# Y187.net
KiCad netlist of a schematic drawn in EAGLE
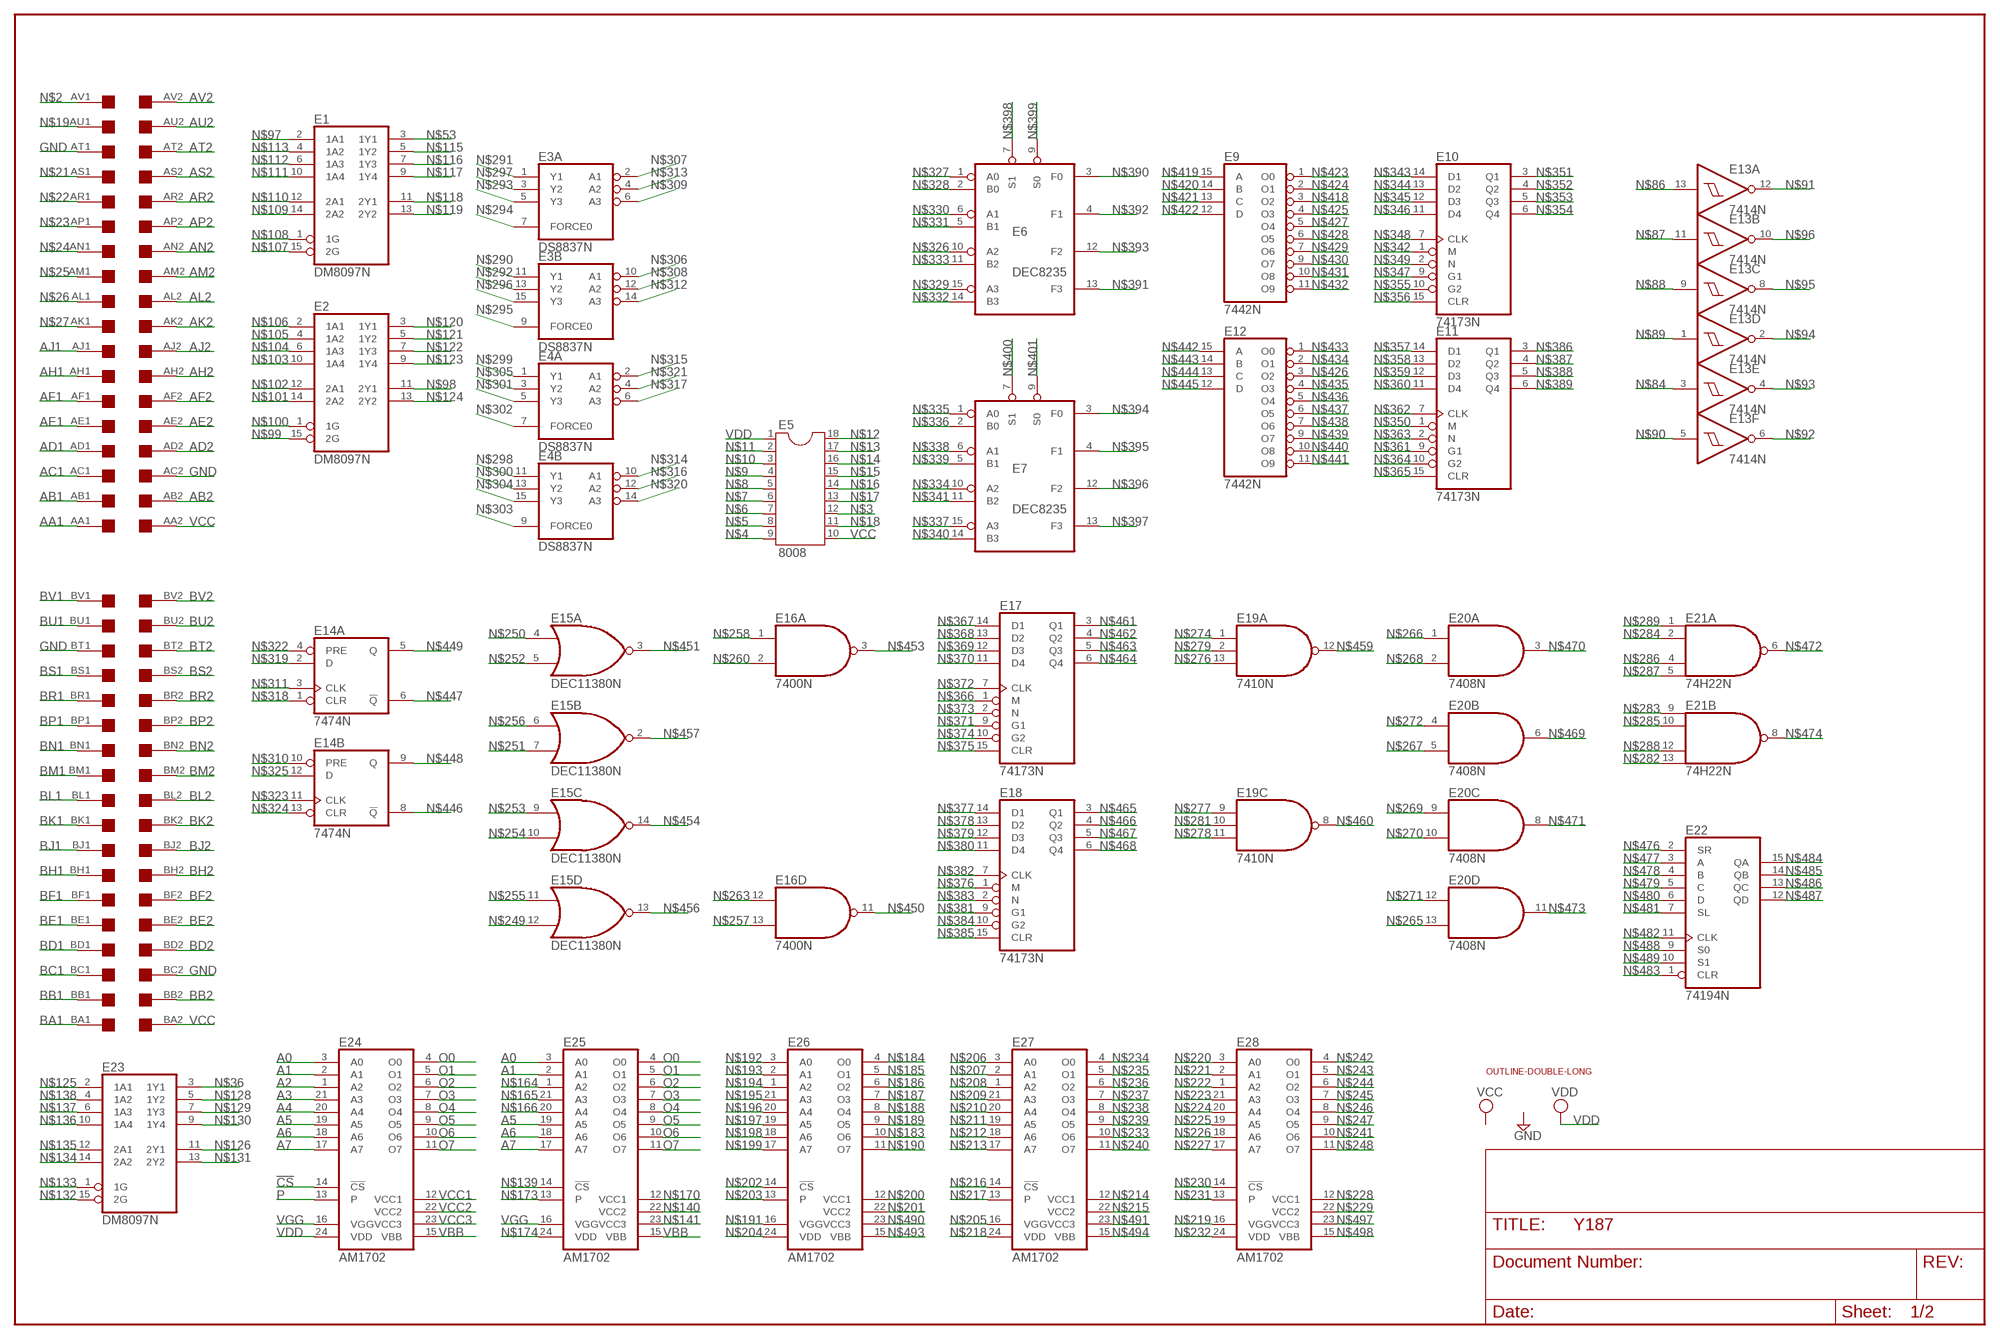
[diagram p0: schematic, sheet 1]
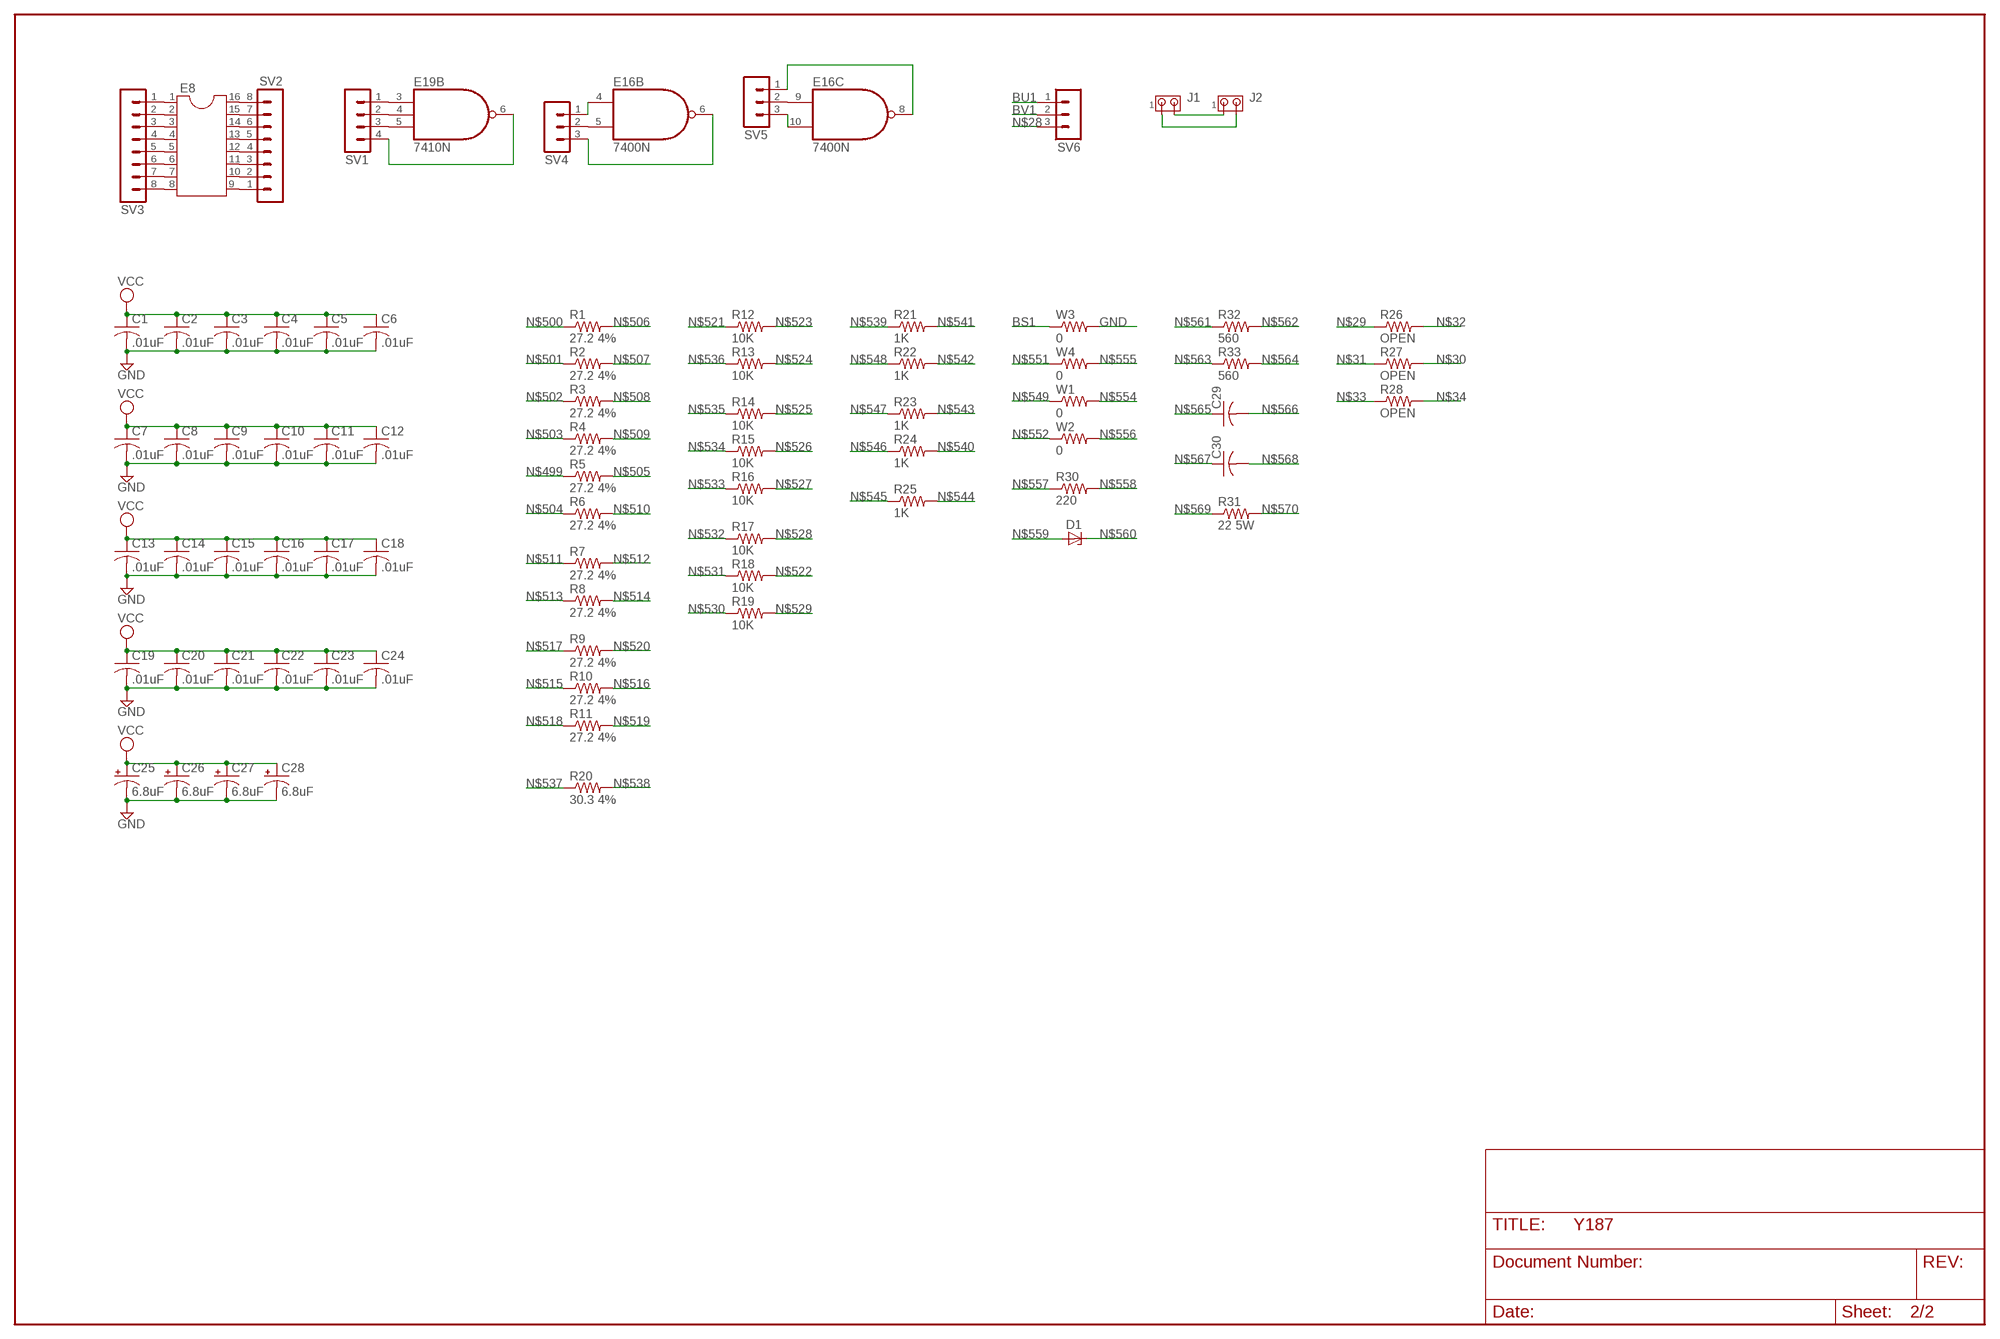
[diagram p1: schematic, sheet 2]

(export (version "E")
  (design (tool "Eeschema 10.0.6"))
  (components
    (comp (ref "C1")
      (value ".01uF")
      (footprint "eagle-import:C075-032X103")
      (libsource (lib "eagle-import") (part "C-US075-032X103"))
    )
    (comp (ref "C2")
      (value ".01uF")
      (footprint "eagle-import:C075-032X103")
      (libsource (lib "eagle-import") (part "C-US075-032X103"))
    )
    (comp (ref "C3")
      (value ".01uF")
      (footprint "eagle-import:C075-032X103")
      (libsource (lib "eagle-import") (part "C-US075-032X103"))
    )
    (comp (ref "C4")
      (value ".01uF")
      (footprint "eagle-import:C075-032X103")
      (libsource (lib "eagle-import") (part "C-US075-032X103"))
    )
    (comp (ref "C5")
      (value ".01uF")
      (footprint "eagle-import:C075-032X103")
      (libsource (lib "eagle-import") (part "C-US075-032X103"))
    )
    (comp (ref "C6")
      (value ".01uF")
      (footprint "eagle-import:C075-032X103")
      (libsource (lib "eagle-import") (part "C-US075-032X103"))
    )
    (comp (ref "C7")
      (value ".01uF")
      (footprint "eagle-import:C075-032X103")
      (libsource (lib "eagle-import") (part "C-US075-032X103"))
    )
    (comp (ref "C8")
      (value ".01uF")
      (footprint "eagle-import:C075-032X103")
      (libsource (lib "eagle-import") (part "C-US075-032X103"))
    )
    (comp (ref "C9")
      (value ".01uF")
      (footprint "eagle-import:C075-032X103")
      (libsource (lib "eagle-import") (part "C-US075-032X103"))
    )
    (comp (ref "C10")
      (value ".01uF")
      (footprint "eagle-import:C075-032X103")
      (libsource (lib "eagle-import") (part "C-US075-032X103"))
    )
    (comp (ref "C11")
      (value ".01uF")
      (footprint "eagle-import:C075-032X103")
      (libsource (lib "eagle-import") (part "C-US075-032X103"))
    )
    (comp (ref "C12")
      (value ".01uF")
      (footprint "eagle-import:C075-032X103")
      (libsource (lib "eagle-import") (part "C-US075-032X103"))
    )
    (comp (ref "C13")
      (value ".01uF")
      (footprint "eagle-import:C075-032X103")
      (libsource (lib "eagle-import") (part "C-US075-032X103"))
    )
    (comp (ref "C14")
      (value ".01uF")
      (footprint "eagle-import:C075-032X103")
      (libsource (lib "eagle-import") (part "C-US075-032X103"))
    )
    (comp (ref "C15")
      (value ".01uF")
      (footprint "eagle-import:C075-032X103")
      (libsource (lib "eagle-import") (part "C-US075-032X103"))
    )
    (comp (ref "C16")
      (value ".01uF")
      (footprint "eagle-import:C075-032X103")
      (libsource (lib "eagle-import") (part "C-US075-032X103"))
    )
    (comp (ref "C17")
      (value ".01uF")
      (footprint "eagle-import:C075-032X103")
      (libsource (lib "eagle-import") (part "C-US075-032X103"))
    )
    (comp (ref "C18")
      (value ".01uF")
      (footprint "eagle-import:C075-032X103")
      (libsource (lib "eagle-import") (part "C-US075-032X103"))
    )
    (comp (ref "C19")
      (value ".01uF")
      (footprint "eagle-import:C075-032X103")
      (libsource (lib "eagle-import") (part "C-US075-032X103"))
    )
    (comp (ref "C20")
      (value ".01uF")
      (footprint "eagle-import:C075-032X103")
      (libsource (lib "eagle-import") (part "C-US075-032X103"))
    )
    (comp (ref "C21")
      (value ".01uF")
      (footprint "eagle-import:C075-032X103")
      (libsource (lib "eagle-import") (part "C-US075-032X103"))
    )
    (comp (ref "C22")
      (value ".01uF")
      (footprint "eagle-import:C075-032X103")
      (libsource (lib "eagle-import") (part "C-US075-032X103"))
    )
    (comp (ref "C23")
      (value ".01uF")
      (footprint "eagle-import:C075-032X103")
      (libsource (lib "eagle-import") (part "C-US075-032X103"))
    )
    (comp (ref "C24")
      (value ".01uF")
      (footprint "eagle-import:C075-032X103")
      (libsource (lib "eagle-import") (part "C-US075-032X103"))
    )
    (comp (ref "C25")
      (value "6.8uF")
      (footprint "eagle-import:E12-8")
      (libsource (lib "eagle-import") (part "CPOL-USE20-8AXIAL"))
    )
    (comp (ref "C26")
      (value "6.8uF")
      (footprint "eagle-import:E12-8")
      (libsource (lib "eagle-import") (part "CPOL-USE20-8AXIAL"))
    )
    (comp (ref "C27")
      (value "6.8uF")
      (footprint "eagle-import:E12-8")
      (libsource (lib "eagle-import") (part "CPOL-USE20-8AXIAL"))
    )
    (comp (ref "C28")
      (value "6.8uF")
      (footprint "eagle-import:E12-8")
      (libsource (lib "eagle-import") (part "CPOL-USE20-8AXIAL"))
    )
    (comp (ref "C29")
      (value "C-US075-032X103")
      (footprint "eagle-import:C075-032X103")
      (libsource (lib "eagle-import") (part "C-US075-032X103"))
    )
    (comp (ref "C30")
      (value "C-US075-032X103")
      (footprint "eagle-import:C075-032X103")
      (libsource (lib "eagle-import") (part "C-US075-032X103"))
    )
    (comp (ref "D1")
      (value "ZENER-DIODEDO35Z10")
      (footprint "eagle-import:DO35Z10")
      (libsource (lib "eagle-import") (part "ZENER-DIODEDO35Z10"))
    )
    (comp (ref "E8")
      (value "DIL16")
      (footprint "eagle-import:DIL16")
      (libsource (lib "eagle-import") (part "DIL16"))
    )
    (comp (ref "E16")
      (value "7400N")
      (footprint "eagle-import:DIL14")
      (libsource (lib "eagle-import") (part "7400N"))
    )
    (comp (ref "E19")
      (value "7410N")
      (footprint "eagle-import:DIL14")
      (libsource (lib "eagle-import") (part "7410N"))
    )
    (comp (ref "J1")
      (value "MTA02-100")
      (footprint "eagle-import:10X02MTA")
      (libsource (lib "eagle-import") (part "MTA02-100"))
    )
    (comp (ref "J2")
      (value "MTA02-100")
      (footprint "eagle-import:10X02MTA")
      (libsource (lib "eagle-import") (part "MTA02-100"))
    )
    (comp (ref "R1")
      (value "27.2 4%")
      (footprint "eagle-import:0207_10")
      (libsource (lib "eagle-import") (part "R-US_0207/10"))
    )
    (comp (ref "R2")
      (value "27.2 4%")
      (footprint "eagle-import:0207_10")
      (libsource (lib "eagle-import") (part "R-US_0207/10"))
    )
    (comp (ref "R3")
      (value "27.2 4%")
      (footprint "eagle-import:0207_10")
      (libsource (lib "eagle-import") (part "R-US_0207/10"))
    )
    (comp (ref "R4")
      (value "27.2 4%")
      (footprint "eagle-import:0207_10")
      (libsource (lib "eagle-import") (part "R-US_0207/10"))
    )
    (comp (ref "R5")
      (value "27.2 4%")
      (footprint "eagle-import:0207_10")
      (libsource (lib "eagle-import") (part "R-US_0207/10"))
    )
    (comp (ref "R6")
      (value "27.2 4%")
      (footprint "eagle-import:0207_10")
      (libsource (lib "eagle-import") (part "R-US_0207/10"))
    )
    (comp (ref "R7")
      (value "27.2 4%")
      (footprint "eagle-import:0207_10")
      (libsource (lib "eagle-import") (part "R-US_0207/10"))
    )
    (comp (ref "R8")
      (value "27.2 4%")
      (footprint "eagle-import:0207_10")
      (libsource (lib "eagle-import") (part "R-US_0207/10"))
    )
    (comp (ref "R9")
      (value "27.2 4%")
      (footprint "eagle-import:0207_10")
      (libsource (lib "eagle-import") (part "R-US_0207/10"))
    )
    (comp (ref "R10")
      (value "27.2 4%")
      (footprint "eagle-import:0207_10")
      (libsource (lib "eagle-import") (part "R-US_0207/10"))
    )
    (comp (ref "R11")
      (value "27.2 4%")
      (footprint "eagle-import:0207_10")
      (libsource (lib "eagle-import") (part "R-US_0207/10"))
    )
    (comp (ref "R12")
      (value "10K")
      (footprint "eagle-import:0207_10")
      (libsource (lib "eagle-import") (part "R-US_0207/10"))
    )
    (comp (ref "R13")
      (value "10K")
      (footprint "eagle-import:0207_10")
      (libsource (lib "eagle-import") (part "R-US_0207/10"))
    )
    (comp (ref "R14")
      (value "10K")
      (footprint "eagle-import:0207_10")
      (libsource (lib "eagle-import") (part "R-US_0207/10"))
    )
    (comp (ref "R15")
      (value "10K")
      (footprint "eagle-import:0207_10")
      (libsource (lib "eagle-import") (part "R-US_0207/10"))
    )
    (comp (ref "R16")
      (value "10K")
      (footprint "eagle-import:0207_10")
      (libsource (lib "eagle-import") (part "R-US_0207/10"))
    )
    (comp (ref "R17")
      (value "10K")
      (footprint "eagle-import:0207_10")
      (libsource (lib "eagle-import") (part "R-US_0207/10"))
    )
    (comp (ref "R18")
      (value "10K")
      (footprint "eagle-import:0207_10")
      (libsource (lib "eagle-import") (part "R-US_0207/10"))
    )
    (comp (ref "R19")
      (value "10K")
      (footprint "eagle-import:0207_10")
      (libsource (lib "eagle-import") (part "R-US_0207/10"))
    )
    (comp (ref "R20")
      (value "30.3 4%")
      (footprint "eagle-import:0207_10")
      (libsource (lib "eagle-import") (part "R-US_0207/10"))
    )
    (comp (ref "R21")
      (value "1K")
      (footprint "eagle-import:0207_10")
      (libsource (lib "eagle-import") (part "R-US_0207/10"))
    )
    (comp (ref "R22")
      (value "1K")
      (footprint "eagle-import:0207_10")
      (libsource (lib "eagle-import") (part "R-US_0207/10"))
    )
    (comp (ref "R23")
      (value "1K")
      (footprint "eagle-import:0207_10")
      (libsource (lib "eagle-import") (part "R-US_0207/10"))
    )
    (comp (ref "R24")
      (value "1K")
      (footprint "eagle-import:0207_10")
      (libsource (lib "eagle-import") (part "R-US_0207/10"))
    )
    (comp (ref "R25")
      (value "1K")
      (footprint "eagle-import:0207_10")
      (libsource (lib "eagle-import") (part "R-US_0207/10"))
    )
    (comp (ref "R26")
      (value "OPEN")
      (footprint "eagle-import:0207_10")
      (libsource (lib "eagle-import") (part "R-US_0207/10"))
    )
    (comp (ref "R27")
      (value "OPEN")
      (footprint "eagle-import:0207_10")
      (libsource (lib "eagle-import") (part "R-US_0207/10"))
    )
    (comp (ref "R28")
      (value "OPEN")
      (footprint "eagle-import:0207_10")
      (libsource (lib "eagle-import") (part "R-US_0207/10"))
    )
    (comp (ref "R30")
      (value "220")
      (footprint "eagle-import:0207_10")
      (libsource (lib "eagle-import") (part "R-US_0207/10"))
    )
    (comp (ref "R31")
      (value "22 5W")
      (footprint "eagle-import:0617_22")
      (libsource (lib "eagle-import") (part "R-US_0617/22"))
    )
    (comp (ref "R32")
      (value "560")
      (footprint "eagle-import:0207_10")
      (libsource (lib "eagle-import") (part "R-US_0207/10"))
    )
    (comp (ref "R33")
      (value "560")
      (footprint "eagle-import:0207_10")
      (libsource (lib "eagle-import") (part "R-US_0207/10"))
    )
    (comp (ref "SV1")
      (value "MA04-1")
      (footprint "eagle-import:MA04-1")
      (libsource (lib "eagle-import") (part "MA04-1"))
    )
    (comp (ref "SV2")
      (value "MA08-1")
      (footprint "eagle-import:MA08-1")
      (libsource (lib "eagle-import") (part "MA08-1"))
    )
    (comp (ref "SV3")
      (value "MA08-1")
      (footprint "eagle-import:MA08-1")
      (libsource (lib "eagle-import") (part "MA08-1"))
    )
    (comp (ref "SV4")
      (value "MA03-1")
      (footprint "eagle-import:MA03-1")
      (libsource (lib "eagle-import") (part "MA03-1"))
    )
    (comp (ref "SV5")
      (value "MA03-1")
      (footprint "eagle-import:MA03-1")
      (libsource (lib "eagle-import") (part "MA03-1"))
    )
    (comp (ref "SV6")
      (value "MA03-1")
      (footprint "eagle-import:MA03-1")
      (libsource (lib "eagle-import") (part "MA03-1"))
    )
    (comp (ref "W1")
      (value "0")
      (footprint "eagle-import:0207_10")
      (libsource (lib "eagle-import") (part "R-US_0207/10"))
    )
    (comp (ref "W2")
      (value "0")
      (footprint "eagle-import:0207_10")
      (libsource (lib "eagle-import") (part "R-US_0207/10"))
    )
    (comp (ref "W3")
      (value "0")
      (footprint "eagle-import:0207_10")
      (libsource (lib "eagle-import") (part "R-US_0207/10"))
    )
    (comp (ref "W4")
      (value "0")
      (footprint "eagle-import:0207_10")
      (libsource (lib "eagle-import") (part "R-US_0207/10"))
    )
    (comp (ref "E1")
      (value "DM8097N")
      (footprint "eagle-import:DIL16")
      (libsource (lib "eagle-import") (part "74367N"))
    )
    (comp (ref "E2")
      (value "DM8097N")
      (footprint "eagle-import:DIL16")
      (libsource (lib "eagle-import") (part "74367N"))
    )
    (comp (ref "E3")
      (value "DS8837N")
      (footprint "eagle-import:DIL16")
      (libsource (lib "eagle-import") (part "DS8837N"))
    )
    (comp (ref "E4")
      (value "DS8837N")
      (footprint "eagle-import:DIL16")
      (libsource (lib "eagle-import") (part "DS8837N"))
    )
    (comp (ref "E5")
      (value "8008")
      (footprint "eagle-import:DIL18")
      (libsource (lib "eagle-import") (part "DIL18"))
    )
    (comp (ref "E6")
      (value "DEC8235")
      (footprint "eagle-import:DIL16")
      (libsource (lib "eagle-import") (part "DEC8235"))
    )
    (comp (ref "E7")
      (value "DEC8235")
      (footprint "eagle-import:DIL16")
      (libsource (lib "eagle-import") (part "DEC8235"))
    )
    (comp (ref "E9")
      (value "7442N")
      (footprint "eagle-import:DIL16")
      (libsource (lib "eagle-import") (part "7442NLS"))
    )
    (comp (ref "E10")
      (value "74173N")
      (footprint "eagle-import:DIL16")
      (libsource (lib "eagle-import") (part "74173NLS"))
    )
    (comp (ref "E11")
      (value "74173N")
      (footprint "eagle-import:DIL16")
      (libsource (lib "eagle-import") (part "74173NLS"))
    )
    (comp (ref "E12")
      (value "7442N")
      (footprint "eagle-import:DIL16")
      (libsource (lib "eagle-import") (part "7442NLS"))
    )
    (comp (ref "E13")
      (value "7414N")
      (footprint "eagle-import:DIL14")
      (libsource (lib "eagle-import") (part "7414N"))
    )
    (comp (ref "E14")
      (value "7474N")
      (footprint "eagle-import:DIL14")
      (libsource (lib "eagle-import") (part "7474NS"))
    )
    (comp (ref "E15")
      (value "DEC11380N")
      (footprint "eagle-import:DIL14")
      (libsource (lib "eagle-import") (part "SP380N"))
    )
    (comp (ref "E17")
      (value "74173N")
      (footprint "eagle-import:DIL16")
      (libsource (lib "eagle-import") (part "74173NLS"))
    )
    (comp (ref "E18")
      (value "74173N")
      (footprint "eagle-import:DIL16")
      (libsource (lib "eagle-import") (part "74173NLS"))
    )
    (comp (ref "E20")
      (value "7408N")
      (footprint "eagle-import:DIL14")
      (libsource (lib "eagle-import") (part "7408NLS"))
    )
    (comp (ref "E21")
      (value "74H22N")
      (footprint "eagle-import:DIL14")
      (libsource (lib "eagle-import") (part "7422N"))
    )
    (comp (ref "E22")
      (value "74194N")
      (footprint "eagle-import:DIL16")
      (libsource (lib "eagle-import") (part "74194NLS"))
    )
    (comp (ref "E23")
      (value "DM8097N")
      (footprint "eagle-import:DIL16")
      (libsource (lib "eagle-import") (part "74367N"))
    )
    (comp (ref "E24")
      (value "AM1702")
      (footprint "eagle-import:DIL24")
      (libsource (lib "eagle-import") (part "AM1702"))
    )
    (comp (ref "E25")
      (value "AM1702")
      (footprint "eagle-import:DIL24")
      (libsource (lib "eagle-import") (part "AM1702"))
    )
    (comp (ref "E26")
      (value "AM1702")
      (footprint "eagle-import:DIL24")
      (libsource (lib "eagle-import") (part "AM1702"))
    )
    (comp (ref "E27")
      (value "AM1702")
      (footprint "eagle-import:DIL24")
      (libsource (lib "eagle-import") (part "AM1702"))
    )
    (comp (ref "E28")
      (value "AM1702")
      (footprint "eagle-import:DIL24")
      (libsource (lib "eagle-import") (part "AM1702"))
    )
    (comp (ref "U$1")
      (value "OUTLINE-DOUBLE-LONG")
      (footprint "eagle-import:DOUBLE-LONG")
      (libsource (lib "eagle-import") (part "OUTLINE-DOUBLE-LONG"))
    )
    (comp (ref "U$2")
      (value "DOUBLE")
      (footprint "eagle-import:EDGE-CON4")
      (libsource (lib "eagle-import") (part "DOUBLE"))
    )
  )
  (nets
    (net (code "1") (name "A0") (class "Default")
      (node (ref "E24") (pin "3") (pinfunction "A0_3") (pintype "input"))
      (node (ref "E25") (pin "3") (pinfunction "A0_3") (pintype "input"))
    )
    (net (code "2") (name "A1") (class "Default")
      (node (ref "E24") (pin "2") (pinfunction "A1_2") (pintype "input"))
      (node (ref "E25") (pin "2") (pinfunction "A1_2") (pintype "input"))
    )
    (net (code "3") (name "A2") (class "Default")
      (node (ref "E24") (pin "1") (pinfunction "A2_1") (pintype "input"))
    )
    (net (code "4") (name "A3") (class "Default")
      (node (ref "E24") (pin "21") (pinfunction "A3_21") (pintype "input"))
    )
    (net (code "5") (name "A4") (class "Default")
      (node (ref "E24") (pin "20") (pinfunction "A4_20") (pintype "input"))
    )
    (net (code "6") (name "A5") (class "Default")
      (node (ref "E24") (pin "19") (pinfunction "A5_19") (pintype "input"))
      (node (ref "E25") (pin "19") (pinfunction "A5_19") (pintype "input"))
    )
    (net (code "7") (name "A6") (class "Default")
      (node (ref "E24") (pin "18") (pinfunction "A6_18") (pintype "input"))
      (node (ref "E25") (pin "18") (pinfunction "A6_18") (pintype "input"))
    )
    (net (code "8") (name "A7") (class "Default")
      (node (ref "E24") (pin "17") (pinfunction "A7_17") (pintype "input"))
      (node (ref "E25") (pin "17") (pinfunction "A7_17") (pintype "input"))
    )
    (net (code "9") (name "AA1") (class "Default")
      (node (ref "U$2") (pin "AA1") (pinfunction "1_AA1") (pintype "bidirectional"))
    )
    (net (code "10") (name "AB1") (class "Default")
      (node (ref "U$2") (pin "AB1") (pinfunction "1_AB1") (pintype "bidirectional"))
    )
    (net (code "11") (name "AB2") (class "Default")
      (node (ref "U$2") (pin "AB2") (pinfunction "1_AB2") (pintype "bidirectional"))
    )
    (net (code "12") (name "AC1") (class "Default")
      (node (ref "U$2") (pin "AC1") (pinfunction "1_AC1") (pintype "bidirectional"))
    )
    (net (code "13") (name "AD1") (class "Default")
      (node (ref "U$2") (pin "AD1") (pinfunction "1_AD1") (pintype "bidirectional"))
    )
    (net (code "14") (name "AD2") (class "Default")
      (node (ref "U$2") (pin "AD2") (pinfunction "1_AD2") (pintype "bidirectional"))
    )
    (net (code "15") (name "AE1") (class "Default")
      (node (ref "U$2") (pin "AE1") (pinfunction "1_AE1") (pintype "bidirectional"))
    )
    (net (code "16") (name "AE2") (class "Default")
      (node (ref "U$2") (pin "AE2") (pinfunction "1_AE2") (pintype "bidirectional"))
    )
    (net (code "17") (name "AF1") (class "Default")
      (node (ref "U$2") (pin "AF1") (pinfunction "1_AF1") (pintype "bidirectional"))
    )
    (net (code "18") (name "AF2") (class "Default")
      (node (ref "U$2") (pin "AF2") (pinfunction "1_AF2") (pintype "bidirectional"))
    )
    (net (code "19") (name "AH1") (class "Default")
      (node (ref "U$2") (pin "AH1") (pinfunction "1_AH1") (pintype "bidirectional"))
    )
    (net (code "20") (name "AH2") (class "Default")
      (node (ref "U$2") (pin "AH2") (pinfunction "1_AH2") (pintype "bidirectional"))
    )
    (net (code "21") (name "AJ1") (class "Default")
      (node (ref "U$2") (pin "AJ1") (pinfunction "1_AJ1") (pintype "bidirectional"))
    )
    (net (code "22") (name "AJ2") (class "Default")
      (node (ref "U$2") (pin "AJ2") (pinfunction "1_AJ2") (pintype "bidirectional"))
    )
    (net (code "23") (name "AK2") (class "Default")
      (node (ref "U$2") (pin "AK2") (pinfunction "1_AK2") (pintype "bidirectional"))
    )
    (net (code "24") (name "AL2") (class "Default")
      (node (ref "U$2") (pin "AL2") (pinfunction "1_AL2") (pintype "bidirectional"))
    )
    (net (code "25") (name "AM2") (class "Default")
      (node (ref "U$2") (pin "AM2") (pinfunction "1_AM2") (pintype "bidirectional"))
    )
    (net (code "26") (name "AN2") (class "Default")
      (node (ref "U$2") (pin "AN2") (pinfunction "1_AN2") (pintype "bidirectional"))
    )
    (net (code "27") (name "AP2") (class "Default")
      (node (ref "U$2") (pin "AP2") (pinfunction "1_AP2") (pintype "bidirectional"))
    )
    (net (code "28") (name "AR2") (class "Default")
      (node (ref "U$2") (pin "AR2") (pinfunction "1_AR2") (pintype "bidirectional"))
    )
    (net (code "29") (name "AS2") (class "Default")
      (node (ref "U$2") (pin "AS2") (pinfunction "1_AS2") (pintype "bidirectional"))
    )
    (net (code "30") (name "AT2") (class "Default")
      (node (ref "U$2") (pin "AT2") (pinfunction "1_AT2") (pintype "bidirectional"))
    )
    (net (code "31") (name "AU2") (class "Default")
      (node (ref "U$2") (pin "AU2") (pinfunction "1_AU2") (pintype "bidirectional"))
    )
    (net (code "32") (name "AV2") (class "Default")
      (node (ref "U$2") (pin "AV2") (pinfunction "1_AV2") (pintype "bidirectional"))
    )
    (net (code "33") (name "BA1") (class "Default")
      (node (ref "U$2") (pin "BA1") (pinfunction "1_BA1") (pintype "bidirectional"))
    )
    (net (code "34") (name "BB1") (class "Default")
      (node (ref "U$2") (pin "BB1") (pinfunction "1_BB1") (pintype "bidirectional"))
    )
    (net (code "35") (name "BB2") (class "Default")
      (node (ref "U$2") (pin "BB2") (pinfunction "1_BB2") (pintype "bidirectional"))
    )
    (net (code "36") (name "BC1") (class "Default")
      (node (ref "U$2") (pin "BC1") (pinfunction "1_BC1") (pintype "bidirectional"))
    )
    (net (code "37") (name "BD1") (class "Default")
      (node (ref "U$2") (pin "BD1") (pinfunction "1_BD1") (pintype "bidirectional"))
    )
    (net (code "38") (name "BD2") (class "Default")
      (node (ref "U$2") (pin "BD2") (pinfunction "1_BD2") (pintype "bidirectional"))
    )
    (net (code "39") (name "BE1") (class "Default")
      (node (ref "U$2") (pin "BE1") (pinfunction "1_BE1") (pintype "bidirectional"))
    )
    (net (code "40") (name "BE2") (class "Default")
      (node (ref "U$2") (pin "BE2") (pinfunction "1_BE2") (pintype "bidirectional"))
    )
    (net (code "41") (name "BF1") (class "Default")
      (node (ref "U$2") (pin "BF1") (pinfunction "1_BF1") (pintype "bidirectional"))
    )
    (net (code "42") (name "BF2") (class "Default")
      (node (ref "U$2") (pin "BF2") (pinfunction "1_BF2") (pintype "bidirectional"))
    )
    (net (code "43") (name "BH1") (class "Default")
      (node (ref "U$2") (pin "BH1") (pinfunction "1_BH1") (pintype "bidirectional"))
    )
    (net (code "44") (name "BH2") (class "Default")
      (node (ref "U$2") (pin "BH2") (pinfunction "1_BH2") (pintype "bidirectional"))
    )
    (net (code "45") (name "BJ1") (class "Default")
      (node (ref "U$2") (pin "BJ1") (pinfunction "1_BJ1") (pintype "bidirectional"))
    )
    (net (code "46") (name "BJ2") (class "Default")
      (node (ref "U$2") (pin "BJ2") (pinfunction "1_BJ2") (pintype "bidirectional"))
    )
    (net (code "47") (name "BK1") (class "Default")
      (node (ref "U$2") (pin "BK1") (pinfunction "1_BK1") (pintype "bidirectional"))
    )
    (net (code "48") (name "BK2") (class "Default")
      (node (ref "U$2") (pin "BK2") (pinfunction "1_BK2") (pintype "bidirectional"))
    )
    (net (code "49") (name "BL1") (class "Default")
      (node (ref "U$2") (pin "BL1") (pinfunction "1_BL1") (pintype "bidirectional"))
    )
    (net (code "50") (name "BL2") (class "Default")
      (node (ref "U$2") (pin "BL2") (pinfunction "1_BL2") (pintype "bidirectional"))
    )
    (net (code "51") (name "BM1") (class "Default")
      (node (ref "U$2") (pin "BM1") (pinfunction "1_BM1") (pintype "bidirectional"))
    )
    (net (code "52") (name "BM2") (class "Default")
      (node (ref "U$2") (pin "BM2") (pinfunction "1_BM2") (pintype "bidirectional"))
    )
    (net (code "53") (name "BN1") (class "Default")
      (node (ref "U$2") (pin "BN1") (pinfunction "1_BN1") (pintype "bidirectional"))
    )
    (net (code "54") (name "BN2") (class "Default")
      (node (ref "U$2") (pin "BN2") (pinfunction "1_BN2") (pintype "bidirectional"))
    )
    (net (code "55") (name "BP1") (class "Default")
      (node (ref "U$2") (pin "BP1") (pinfunction "1_BP1") (pintype "bidirectional"))
    )
    (net (code "56") (name "BP2") (class "Default")
      (node (ref "U$2") (pin "BP2") (pinfunction "1_BP2") (pintype "bidirectional"))
    )
    (net (code "57") (name "BR1") (class "Default")
      (node (ref "U$2") (pin "BR1") (pinfunction "1_BR1") (pintype "bidirectional"))
    )
    (net (code "58") (name "BR2") (class "Default")
      (node (ref "U$2") (pin "BR2") (pinfunction "1_BR2") (pintype "bidirectional"))
    )
    (net (code "59") (name "BS1") (class "Default")
      (node (ref "U$2") (pin "BS1") (pinfunction "1_BS1") (pintype "bidirectional"))
      (node (ref "W3") (pin "1") (pinfunction "1_1") (pintype "passive"))
    )
    (net (code "60") (name "BS2") (class "Default")
      (node (ref "U$2") (pin "BS2") (pinfunction "1_BS2") (pintype "bidirectional"))
    )
    (net (code "61") (name "BT2") (class "Default")
      (node (ref "U$2") (pin "BT2") (pinfunction "1_BT2") (pintype "bidirectional"))
    )
    (net (code "62") (name "BU1") (class "Default")
      (node (ref "SV6") (pin "1") (pinfunction "1_1") (pintype "passive"))
      (node (ref "U$2") (pin "BU1") (pinfunction "1_BU1") (pintype "bidirectional"))
    )
    (net (code "63") (name "BU2") (class "Default")
      (node (ref "U$2") (pin "BU2") (pinfunction "1_BU2") (pintype "bidirectional"))
    )
    (net (code "64") (name "BV1") (class "Default")
      (node (ref "SV6") (pin "2") (pinfunction "2_2") (pintype "passive"))
      (node (ref "U$2") (pin "BV1") (pinfunction "1_BV1") (pintype "bidirectional"))
    )
    (net (code "65") (name "BV2") (class "Default")
      (node (ref "U$2") (pin "BV2") (pinfunction "1_BV2") (pintype "bidirectional"))
    )
    (net (code "66") (name "GND") (class "Default")
      (node (ref "C1") (pin "2") (pinfunction "2_2") (pintype "passive"))
      (node (ref "C10") (pin "2") (pinfunction "2_2") (pintype "passive"))
      (node (ref "C11") (pin "2") (pinfunction "2_2") (pintype "passive"))
      (node (ref "C12") (pin "2") (pinfunction "2_2") (pintype "passive"))
      (node (ref "C13") (pin "2") (pinfunction "2_2") (pintype "passive"))
      (node (ref "C14") (pin "2") (pinfunction "2_2") (pintype "passive"))
      (node (ref "C15") (pin "2") (pinfunction "2_2") (pintype "passive"))
      (node (ref "C16") (pin "2") (pinfunction "2_2") (pintype "passive"))
      (node (ref "C17") (pin "2") (pinfunction "2_2") (pintype "passive"))
      (node (ref "C18") (pin "2") (pinfunction "2_2") (pintype "passive"))
      (node (ref "C19") (pin "2") (pinfunction "2_2") (pintype "passive"))
      (node (ref "C2") (pin "2") (pinfunction "2_2") (pintype "passive"))
      (node (ref "C20") (pin "2") (pinfunction "2_2") (pintype "passive"))
      (node (ref "C21") (pin "2") (pinfunction "2_2") (pintype "passive"))
      (node (ref "C22") (pin "2") (pinfunction "2_2") (pintype "passive"))
      (node (ref "C23") (pin "2") (pinfunction "2_2") (pintype "passive"))
      (node (ref "C24") (pin "2") (pinfunction "2_2") (pintype "passive"))
      (node (ref "C25") (pin "-") (pinfunction "-_-") (pintype "passive"))
      (node (ref "C26") (pin "-") (pinfunction "-_-") (pintype "passive"))
      (node (ref "C27") (pin "-") (pinfunction "-_-") (pintype "passive"))
      (node (ref "C28") (pin "-") (pinfunction "-_-") (pintype "passive"))
      (node (ref "C3") (pin "2") (pinfunction "2_2") (pintype "passive"))
      (node (ref "C4") (pin "2") (pinfunction "2_2") (pintype "passive"))
      (node (ref "C5") (pin "2") (pinfunction "2_2") (pintype "passive"))
      (node (ref "C6") (pin "2") (pinfunction "2_2") (pintype "passive"))
      (node (ref "C7") (pin "2") (pinfunction "2_2") (pintype "passive"))
      (node (ref "C8") (pin "2") (pinfunction "2_2") (pintype "passive"))
      (node (ref "C9") (pin "2") (pinfunction "2_2") (pintype "passive"))
      (node (ref "U$2") (pin "AC2") (pinfunction "1_AC2") (pintype "bidirectional"))
      (node (ref "U$2") (pin "AT1") (pinfunction "1_AT1") (pintype "bidirectional"))
      (node (ref "U$2") (pin "BC2") (pinfunction "1_BC2") (pintype "bidirectional"))
      (node (ref "U$2") (pin "BT1") (pinfunction "1_BT1") (pintype "bidirectional"))
      (node (ref "W3") (pin "2") (pinfunction "2_2") (pintype "passive"))
    )
    (net (code "67") (name "N$2") (class "Default")
      (node (ref "U$2") (pin "AV1") (pinfunction "1_AV1") (pintype "bidirectional"))
    )
    (net (code "68") (name "N$3") (class "Default")
      (node (ref "E5") (pin "12") (pinfunction "12_12") (pintype "passive"))
    )
    (net (code "69") (name "N$4") (class "Default")
      (node (ref "E5") (pin "9") (pinfunction "9_9") (pintype "passive"))
    )
    (net (code "70") (name "N$5") (class "Default")
      (node (ref "E5") (pin "8") (pinfunction "8_8") (pintype "passive"))
    )
    (net (code "71") (name "N$6") (class "Default")
      (node (ref "E5") (pin "7") (pinfunction "7_7") (pintype "passive"))
    )
    (net (code "72") (name "N$7") (class "Default")
      (node (ref "E5") (pin "6") (pinfunction "6_6") (pintype "passive"))
    )
    (net (code "73") (name "N$8") (class "Default")
      (node (ref "E5") (pin "5") (pinfunction "5_5") (pintype "passive"))
    )
    (net (code "74") (name "N$9") (class "Default")
      (node (ref "E5") (pin "4") (pinfunction "4_4") (pintype "passive"))
    )
    (net (code "75") (name "N$10") (class "Default")
      (node (ref "E5") (pin "3") (pinfunction "3_3") (pintype "passive"))
    )
    (net (code "76") (name "N$11") (class "Default")
      (node (ref "E5") (pin "2") (pinfunction "2_2") (pintype "passive"))
    )
    (net (code "77") (name "N$12") (class "Default")
      (node (ref "E5") (pin "18") (pinfunction "18_18") (pintype "passive"))
    )
    (net (code "78") (name "N$13") (class "Default")
      (node (ref "E5") (pin "17") (pinfunction "17_17") (pintype "passive"))
    )
    (net (code "79") (name "N$14") (class "Default")
      (node (ref "E5") (pin "16") (pinfunction "16_16") (pintype "passive"))
    )
    (net (code "80") (name "N$15") (class "Default")
      (node (ref "E5") (pin "15") (pinfunction "15_15") (pintype "passive"))
    )
    (net (code "81") (name "N$16") (class "Default")
      (node (ref "E5") (pin "14") (pinfunction "14_14") (pintype "passive"))
    )
    (net (code "82") (name "N$17") (class "Default")
      (node (ref "E5") (pin "13") (pinfunction "13_13") (pintype "passive"))
    )
    (net (code "83") (name "N$18") (class "Default")
      (node (ref "E5") (pin "11") (pinfunction "11_11") (pintype "passive"))
    )
    (net (code "84") (name "N$19") (class "Default")
      (node (ref "U$2") (pin "AU1") (pinfunction "1_AU1") (pintype "bidirectional"))
    )
    (net (code "85") (name "N$21") (class "Default")
      (node (ref "U$2") (pin "AS1") (pinfunction "1_AS1") (pintype "bidirectional"))
    )
    (net (code "86") (name "N$22") (class "Default")
      (node (ref "U$2") (pin "AR1") (pinfunction "1_AR1") (pintype "bidirectional"))
    )
    (net (code "87") (name "N$23") (class "Default")
      (node (ref "U$2") (pin "AP1") (pinfunction "1_AP1") (pintype "bidirectional"))
    )
    (net (code "88") (name "N$24") (class "Default")
      (node (ref "U$2") (pin "AN1") (pinfunction "1_AN1") (pintype "bidirectional"))
    )
    (net (code "89") (name "N$25") (class "Default")
      (node (ref "U$2") (pin "AM1") (pinfunction "1_AM1") (pintype "bidirectional"))
    )
    (net (code "90") (name "N$26") (class "Default")
      (node (ref "U$2") (pin "AL1") (pinfunction "1_AL1") (pintype "bidirectional"))
    )
    (net (code "91") (name "N$27") (class "Default")
      (node (ref "U$2") (pin "AK1") (pinfunction "1_AK1") (pintype "bidirectional"))
    )
    (net (code "92") (name "N$28") (class "Default")
      (node (ref "SV6") (pin "3") (pinfunction "3_3") (pintype "passive"))
    )
    (net (code "93") (name "N$29") (class "Default")
      (node (ref "R26") (pin "1") (pinfunction "1_1") (pintype "passive"))
    )
    (net (code "94") (name "N$30") (class "Default")
      (node (ref "R27") (pin "2") (pinfunction "2_2") (pintype "passive"))
    )
    (net (code "95") (name "N$31") (class "Default")
      (node (ref "R27") (pin "1") (pinfunction "1_1") (pintype "passive"))
    )
    (net (code "96") (name "N$32") (class "Default")
      (node (ref "R26") (pin "2") (pinfunction "2_2") (pintype "passive"))
    )
    (net (code "97") (name "N$33") (class "Default")
      (node (ref "R28") (pin "1") (pinfunction "1_1") (pintype "passive"))
    )
    (net (code "98") (name "N$34") (class "Default")
      (node (ref "R28") (pin "2") (pinfunction "2_2") (pintype "passive"))
    )
    (net (code "99") (name "N$36") (class "Default")
      (node (ref "E23") (pin "3") (pinfunction "1Y1_3") (pintype "tri_state"))
    )
    (net (code "100") (name "N$53") (class "Default")
      (node (ref "E1") (pin "3") (pinfunction "1Y1_3") (pintype "tri_state"))
    )
    (net (code "101") (name "N$84") (class "Default")
      (node (ref "E13") (pin "3") (pinfunction "I_3") (pintype "input"))
    )
    (net (code "102") (name "N$86") (class "Default")
      (node (ref "E13") (pin "13") (pinfunction "I_13") (pintype "input"))
    )
    (net (code "103") (name "N$87") (class "Default")
      (node (ref "E13") (pin "11") (pinfunction "I_11") (pintype "input"))
    )
    (net (code "104") (name "N$88") (class "Default")
      (node (ref "E13") (pin "9") (pinfunction "I_9") (pintype "input"))
    )
    (net (code "105") (name "N$89") (class "Default")
      (node (ref "E13") (pin "1") (pinfunction "I_1") (pintype "input"))
    )
    (net (code "106") (name "N$90") (class "Default")
      (node (ref "E13") (pin "5") (pinfunction "I_5") (pintype "input"))
    )
    (net (code "107") (name "N$91") (class "Default")
      (node (ref "E13") (pin "12") (pinfunction "O_12") (pintype "output"))
    )
    (net (code "108") (name "N$92") (class "Default")
      (node (ref "E13") (pin "6") (pinfunction "O_6") (pintype "output"))
    )
    (net (code "109") (name "N$93") (class "Default")
      (node (ref "E13") (pin "4") (pinfunction "O_4") (pintype "output"))
    )
    (net (code "110") (name "N$94") (class "Default")
      (node (ref "E13") (pin "2") (pinfunction "O_2") (pintype "output"))
    )
    (net (code "111") (name "N$95") (class "Default")
      (node (ref "E13") (pin "8") (pinfunction "O_8") (pintype "output"))
    )
    (net (code "112") (name "N$96") (class "Default")
      (node (ref "E13") (pin "10") (pinfunction "O_10") (pintype "output"))
    )
    (net (code "113") (name "N$97") (class "Default")
      (node (ref "E1") (pin "2") (pinfunction "1A1_2") (pintype "input"))
    )
    (net (code "114") (name "N$98") (class "Default")
      (node (ref "E2") (pin "11") (pinfunction "2Y1_11") (pintype "tri_state"))
    )
    (net (code "115") (name "N$99") (class "Default")
      (node (ref "E2") (pin "15") (pinfunction "2G_15") (pintype "input"))
    )
    (net (code "116") (name "N$100") (class "Default")
      (node (ref "E2") (pin "1") (pinfunction "1G_1") (pintype "input"))
    )
    (net (code "117") (name "N$101") (class "Default")
      (node (ref "E2") (pin "14") (pinfunction "2A2_14") (pintype "input"))
    )
    (net (code "118") (name "N$102") (class "Default")
      (node (ref "E2") (pin "12") (pinfunction "2A1_12") (pintype "input"))
    )
    (net (code "119") (name "N$103") (class "Default")
      (node (ref "E2") (pin "10") (pinfunction "1A4_10") (pintype "input"))
    )
    (net (code "120") (name "N$104") (class "Default")
      (node (ref "E2") (pin "6") (pinfunction "1A3_6") (pintype "input"))
    )
    (net (code "121") (name "N$105") (class "Default")
      (node (ref "E2") (pin "4") (pinfunction "1A2_4") (pintype "input"))
    )
    (net (code "122") (name "N$106") (class "Default")
      (node (ref "E2") (pin "2") (pinfunction "1A1_2") (pintype "input"))
    )
    (net (code "123") (name "N$107") (class "Default")
      (node (ref "E1") (pin "15") (pinfunction "2G_15") (pintype "input"))
    )
    (net (code "124") (name "N$108") (class "Default")
      (node (ref "E1") (pin "1") (pinfunction "1G_1") (pintype "input"))
    )
    (net (code "125") (name "N$109") (class "Default")
      (node (ref "E1") (pin "14") (pinfunction "2A2_14") (pintype "input"))
    )
    (net (code "126") (name "N$110") (class "Default")
      (node (ref "E1") (pin "12") (pinfunction "2A1_12") (pintype "input"))
    )
    (net (code "127") (name "N$111") (class "Default")
      (node (ref "E1") (pin "10") (pinfunction "1A4_10") (pintype "input"))
    )
    (net (code "128") (name "N$112") (class "Default")
      (node (ref "E1") (pin "6") (pinfunction "1A3_6") (pintype "input"))
    )
    (net (code "129") (name "N$113") (class "Default")
      (node (ref "E1") (pin "4") (pinfunction "1A2_4") (pintype "input"))
    )
    (net (code "130") (name "N$115") (class "Default")
      (node (ref "E1") (pin "5") (pinfunction "1Y2_5") (pintype "tri_state"))
    )
    (net (code "131") (name "N$116") (class "Default")
      (node (ref "E1") (pin "7") (pinfunction "1Y3_7") (pintype "tri_state"))
    )
    (net (code "132") (name "N$117") (class "Default")
      (node (ref "E1") (pin "9") (pinfunction "1Y4_9") (pintype "tri_state"))
    )
    (net (code "133") (name "N$118") (class "Default")
      (node (ref "E1") (pin "11") (pinfunction "2Y1_11") (pintype "tri_state"))
    )
    (net (code "134") (name "N$119") (class "Default")
      (node (ref "E1") (pin "13") (pinfunction "2Y2_13") (pintype "tri_state"))
    )
    (net (code "135") (name "N$120") (class "Default")
      (node (ref "E2") (pin "3") (pinfunction "1Y1_3") (pintype "tri_state"))
    )
    (net (code "136") (name "N$121") (class "Default")
      (node (ref "E2") (pin "5") (pinfunction "1Y2_5") (pintype "tri_state"))
    )
    (net (code "137") (name "N$122") (class "Default")
      (node (ref "E2") (pin "7") (pinfunction "1Y3_7") (pintype "tri_state"))
    )
    (net (code "138") (name "N$123") (class "Default")
      (node (ref "E2") (pin "9") (pinfunction "1Y4_9") (pintype "tri_state"))
    )
    (net (code "139") (name "N$124") (class "Default")
      (node (ref "E2") (pin "13") (pinfunction "2Y2_13") (pintype "tri_state"))
    )
    (net (code "140") (name "N$125") (class "Default")
      (node (ref "E23") (pin "2") (pinfunction "1A1_2") (pintype "input"))
    )
    (net (code "141") (name "N$126") (class "Default")
      (node (ref "E23") (pin "11") (pinfunction "2Y1_11") (pintype "tri_state"))
    )
    (net (code "142") (name "N$128") (class "Default")
      (node (ref "E23") (pin "5") (pinfunction "1Y2_5") (pintype "tri_state"))
    )
    (net (code "143") (name "N$129") (class "Default")
      (node (ref "E23") (pin "7") (pinfunction "1Y3_7") (pintype "tri_state"))
    )
    (net (code "144") (name "N$130") (class "Default")
      (node (ref "E23") (pin "9") (pinfunction "1Y4_9") (pintype "tri_state"))
    )
    (net (code "145") (name "N$131") (class "Default")
      (node (ref "E23") (pin "13") (pinfunction "2Y2_13") (pintype "tri_state"))
    )
    (net (code "146") (name "N$132") (class "Default")
      (node (ref "E23") (pin "15") (pinfunction "2G_15") (pintype "input"))
    )
    (net (code "147") (name "N$133") (class "Default")
      (node (ref "E23") (pin "1") (pinfunction "1G_1") (pintype "input"))
    )
    (net (code "148") (name "N$134") (class "Default")
      (node (ref "E23") (pin "14") (pinfunction "2A2_14") (pintype "input"))
    )
    (net (code "149") (name "N$135") (class "Default")
      (node (ref "E23") (pin "12") (pinfunction "2A1_12") (pintype "input"))
    )
    (net (code "150") (name "N$136") (class "Default")
      (node (ref "E23") (pin "10") (pinfunction "1A4_10") (pintype "input"))
    )
    (net (code "151") (name "N$137") (class "Default")
      (node (ref "E23") (pin "6") (pinfunction "1A3_6") (pintype "input"))
    )
    (net (code "152") (name "N$138") (class "Default")
      (node (ref "E23") (pin "4") (pinfunction "1A2_4") (pintype "input"))
    )
    (net (code "153") (name "N$139") (class "Default")
      (node (ref "E25") (pin "14") (pinfunction "~{CS}_14") (pintype "input"))
    )
    (net (code "154") (name "N$140") (class "Default")
      (node (ref "E25") (pin "22") (pinfunction "VCC2_22") (pintype "input"))
    )
    (net (code "155") (name "N$141") (class "Default")
      (node (ref "E25") (pin "23") (pinfunction "VCC3_23") (pintype "input"))
    )
    (net (code "156") (name "N$164") (class "Default")
      (node (ref "E25") (pin "1") (pinfunction "A2_1") (pintype "input"))
    )
    (net (code "157") (name "N$165") (class "Default")
      (node (ref "E25") (pin "21") (pinfunction "A3_21") (pintype "input"))
    )
    (net (code "158") (name "N$166") (class "Default")
      (node (ref "E25") (pin "20") (pinfunction "A4_20") (pintype "input"))
    )
    (net (code "159") (name "N$170") (class "Default")
      (node (ref "E25") (pin "12") (pinfunction "VCC1_12") (pintype "input"))
    )
    (net (code "160") (name "N$173") (class "Default")
      (node (ref "E25") (pin "13") (pinfunction "P_13") (pintype "input"))
    )
    (net (code "161") (name "N$174") (class "Default")
      (node (ref "E25") (pin "24") (pinfunction "VDD_24") (pintype "input"))
    )
    (net (code "162") (name "N$183") (class "Default")
      (node (ref "E26") (pin "10") (pinfunction "O6_10") (pintype "tri_state"))
    )
    (net (code "163") (name "N$184") (class "Default")
      (node (ref "E26") (pin "4") (pinfunction "O0_4") (pintype "tri_state"))
    )
    (net (code "164") (name "N$185") (class "Default")
      (node (ref "E26") (pin "5") (pinfunction "O1_5") (pintype "tri_state"))
    )
    (net (code "165") (name "N$186") (class "Default")
      (node (ref "E26") (pin "6") (pinfunction "O2_6") (pintype "tri_state"))
    )
    (net (code "166") (name "N$187") (class "Default")
      (node (ref "E26") (pin "7") (pinfunction "O3_7") (pintype "tri_state"))
    )
    (net (code "167") (name "N$188") (class "Default")
      (node (ref "E26") (pin "8") (pinfunction "O4_8") (pintype "tri_state"))
    )
    (net (code "168") (name "N$189") (class "Default")
      (node (ref "E26") (pin "9") (pinfunction "O5_9") (pintype "tri_state"))
    )
    (net (code "169") (name "N$190") (class "Default")
      (node (ref "E26") (pin "11") (pinfunction "O7_11") (pintype "tri_state"))
    )
    (net (code "170") (name "N$191") (class "Default")
      (node (ref "E26") (pin "16") (pinfunction "VGG_16") (pintype "input"))
    )
    (net (code "171") (name "N$192") (class "Default")
      (node (ref "E26") (pin "3") (pinfunction "A0_3") (pintype "input"))
    )
    (net (code "172") (name "N$193") (class "Default")
      (node (ref "E26") (pin "2") (pinfunction "A1_2") (pintype "input"))
    )
    (net (code "173") (name "N$194") (class "Default")
      (node (ref "E26") (pin "1") (pinfunction "A2_1") (pintype "input"))
    )
    (net (code "174") (name "N$195") (class "Default")
      (node (ref "E26") (pin "21") (pinfunction "A3_21") (pintype "input"))
    )
    (net (code "175") (name "N$196") (class "Default")
      (node (ref "E26") (pin "20") (pinfunction "A4_20") (pintype "input"))
    )
    (net (code "176") (name "N$197") (class "Default")
      (node (ref "E26") (pin "19") (pinfunction "A5_19") (pintype "input"))
    )
    (net (code "177") (name "N$198") (class "Default")
      (node (ref "E26") (pin "18") (pinfunction "A6_18") (pintype "input"))
    )
    (net (code "178") (name "N$199") (class "Default")
      (node (ref "E26") (pin "17") (pinfunction "A7_17") (pintype "input"))
    )
    (net (code "179") (name "N$200") (class "Default")
      (node (ref "E26") (pin "12") (pinfunction "VCC1_12") (pintype "input"))
    )
    (net (code "180") (name "N$201") (class "Default")
      (node (ref "E26") (pin "22") (pinfunction "VCC2_22") (pintype "input"))
    )
    (net (code "181") (name "N$202") (class "Default")
      (node (ref "E26") (pin "14") (pinfunction "~{CS}_14") (pintype "input"))
    )
    (net (code "182") (name "N$203") (class "Default")
      (node (ref "E26") (pin "13") (pinfunction "P_13") (pintype "input"))
    )
    (net (code "183") (name "N$204") (class "Default")
      (node (ref "E26") (pin "24") (pinfunction "VDD_24") (pintype "input"))
    )
    (net (code "184") (name "N$205") (class "Default")
      (node (ref "E27") (pin "16") (pinfunction "VGG_16") (pintype "input"))
    )
    (net (code "185") (name "N$206") (class "Default")
      (node (ref "E27") (pin "3") (pinfunction "A0_3") (pintype "input"))
    )
    (net (code "186") (name "N$207") (class "Default")
      (node (ref "E27") (pin "2") (pinfunction "A1_2") (pintype "input"))
    )
    (net (code "187") (name "N$208") (class "Default")
      (node (ref "E27") (pin "1") (pinfunction "A2_1") (pintype "input"))
    )
    (net (code "188") (name "N$209") (class "Default")
      (node (ref "E27") (pin "21") (pinfunction "A3_21") (pintype "input"))
    )
    (net (code "189") (name "N$210") (class "Default")
      (node (ref "E27") (pin "20") (pinfunction "A4_20") (pintype "input"))
    )
    (net (code "190") (name "N$211") (class "Default")
      (node (ref "E27") (pin "19") (pinfunction "A5_19") (pintype "input"))
    )
    (net (code "191") (name "N$212") (class "Default")
      (node (ref "E27") (pin "18") (pinfunction "A6_18") (pintype "input"))
    )
    (net (code "192") (name "N$213") (class "Default")
      (node (ref "E27") (pin "17") (pinfunction "A7_17") (pintype "input"))
    )
    (net (code "193") (name "N$214") (class "Default")
      (node (ref "E27") (pin "12") (pinfunction "VCC1_12") (pintype "input"))
    )
    (net (code "194") (name "N$215") (class "Default")
      (node (ref "E27") (pin "22") (pinfunction "VCC2_22") (pintype "input"))
    )
    (net (code "195") (name "N$216") (class "Default")
      (node (ref "E27") (pin "14") (pinfunction "~{CS}_14") (pintype "input"))
    )
    (net (code "196") (name "N$217") (class "Default")
      (node (ref "E27") (pin "13") (pinfunction "P_13") (pintype "input"))
    )
    (net (code "197") (name "N$218") (class "Default")
      (node (ref "E27") (pin "24") (pinfunction "VDD_24") (pintype "input"))
    )
    (net (code "198") (name "N$219") (class "Default")
      (node (ref "E28") (pin "16") (pinfunction "VGG_16") (pintype "input"))
    )
    (net (code "199") (name "N$220") (class "Default")
      (node (ref "E28") (pin "3") (pinfunction "A0_3") (pintype "input"))
    )
    (net (code "200") (name "N$221") (class "Default")
      (node (ref "E28") (pin "2") (pinfunction "A1_2") (pintype "input"))
    )
    (net (code "201") (name "N$222") (class "Default")
      (node (ref "E28") (pin "1") (pinfunction "A2_1") (pintype "input"))
    )
    (net (code "202") (name "N$223") (class "Default")
      (node (ref "E28") (pin "21") (pinfunction "A3_21") (pintype "input"))
    )
    (net (code "203") (name "N$224") (class "Default")
      (node (ref "E28") (pin "20") (pinfunction "A4_20") (pintype "input"))
    )
    (net (code "204") (name "N$225") (class "Default")
      (node (ref "E28") (pin "19") (pinfunction "A5_19") (pintype "input"))
    )
    (net (code "205") (name "N$226") (class "Default")
      (node (ref "E28") (pin "18") (pinfunction "A6_18") (pintype "input"))
    )
    (net (code "206") (name "N$227") (class "Default")
      (node (ref "E28") (pin "17") (pinfunction "A7_17") (pintype "input"))
    )
    (net (code "207") (name "N$228") (class "Default")
      (node (ref "E28") (pin "12") (pinfunction "VCC1_12") (pintype "input"))
    )
    (net (code "208") (name "N$229") (class "Default")
      (node (ref "E28") (pin "22") (pinfunction "VCC2_22") (pintype "input"))
    )
    (net (code "209") (name "N$230") (class "Default")
      (node (ref "E28") (pin "14") (pinfunction "~{CS}_14") (pintype "input"))
    )
    (net (code "210") (name "N$231") (class "Default")
      (node (ref "E28") (pin "13") (pinfunction "P_13") (pintype "input"))
    )
    (net (code "211") (name "N$232") (class "Default")
      (node (ref "E28") (pin "24") (pinfunction "VDD_24") (pintype "input"))
    )
    (net (code "212") (name "N$233") (class "Default")
      (node (ref "E27") (pin "10") (pinfunction "O6_10") (pintype "tri_state"))
    )
    (net (code "213") (name "N$234") (class "Default")
      (node (ref "E27") (pin "4") (pinfunction "O0_4") (pintype "tri_state"))
    )
    (net (code "214") (name "N$235") (class "Default")
      (node (ref "E27") (pin "5") (pinfunction "O1_5") (pintype "tri_state"))
    )
    (net (code "215") (name "N$236") (class "Default")
      (node (ref "E27") (pin "6") (pinfunction "O2_6") (pintype "tri_state"))
    )
    (net (code "216") (name "N$237") (class "Default")
      (node (ref "E27") (pin "7") (pinfunction "O3_7") (pintype "tri_state"))
    )
    (net (code "217") (name "N$238") (class "Default")
      (node (ref "E27") (pin "8") (pinfunction "O4_8") (pintype "tri_state"))
    )
    (net (code "218") (name "N$239") (class "Default")
      (node (ref "E27") (pin "9") (pinfunction "O5_9") (pintype "tri_state"))
    )
    (net (code "219") (name "N$240") (class "Default")
      (node (ref "E27") (pin "11") (pinfunction "O7_11") (pintype "tri_state"))
    )
    (net (code "220") (name "N$241") (class "Default")
      (node (ref "E28") (pin "10") (pinfunction "O6_10") (pintype "tri_state"))
    )
    (net (code "221") (name "N$242") (class "Default")
      (node (ref "E28") (pin "4") (pinfunction "O0_4") (pintype "tri_state"))
    )
    (net (code "222") (name "N$243") (class "Default")
      (node (ref "E28") (pin "5") (pinfunction "O1_5") (pintype "tri_state"))
    )
    (net (code "223") (name "N$244") (class "Default")
      (node (ref "E28") (pin "6") (pinfunction "O2_6") (pintype "tri_state"))
    )
    (net (code "224") (name "N$245") (class "Default")
      (node (ref "E28") (pin "7") (pinfunction "O3_7") (pintype "tri_state"))
    )
    (net (code "225") (name "N$246") (class "Default")
      (node (ref "E28") (pin "8") (pinfunction "O4_8") (pintype "tri_state"))
    )
    (net (code "226") (name "N$247") (class "Default")
      (node (ref "E28") (pin "9") (pinfunction "O5_9") (pintype "tri_state"))
    )
    (net (code "227") (name "N$248") (class "Default")
      (node (ref "E28") (pin "11") (pinfunction "O7_11") (pintype "tri_state"))
    )
    (net (code "228") (name "N$249") (class "Default")
      (node (ref "E15") (pin "12") (pinfunction "I1_12") (pintype "input"))
    )
    (net (code "229") (name "N$250") (class "Default")
      (node (ref "E15") (pin "4") (pinfunction "I0_4") (pintype "input"))
    )
    (net (code "230") (name "N$251") (class "Default")
      (node (ref "E15") (pin "7") (pinfunction "I1_7") (pintype "input"))
    )
    (net (code "231") (name "N$252") (class "Default")
      (node (ref "E15") (pin "5") (pinfunction "I1_5") (pintype "input"))
    )
    (net (code "232") (name "N$253") (class "Default")
      (node (ref "E15") (pin "9") (pinfunction "I0_9") (pintype "input"))
    )
    (net (code "233") (name "N$254") (class "Default")
      (node (ref "E15") (pin "10") (pinfunction "I1_10") (pintype "input"))
    )
    (net (code "234") (name "N$255") (class "Default")
      (node (ref "E15") (pin "11") (pinfunction "I0_11") (pintype "input"))
    )
    (net (code "235") (name "N$256") (class "Default")
      (node (ref "E15") (pin "6") (pinfunction "I0_6") (pintype "input"))
    )
    (net (code "236") (name "N$257") (class "Default")
      (node (ref "E16") (pin "13") (pinfunction "I1_13") (pintype "input"))
    )
    (net (code "237") (name "N$258") (class "Default")
      (node (ref "E16") (pin "1") (pinfunction "I0_1") (pintype "input"))
    )
    (net (code "238") (name "N$260") (class "Default")
      (node (ref "E16") (pin "2") (pinfunction "I1_2") (pintype "input"))
    )
    (net (code "239") (name "N$263") (class "Default")
      (node (ref "E16") (pin "12") (pinfunction "I0_12") (pintype "input"))
    )
    (net (code "240") (name "N$265") (class "Default")
      (node (ref "E20") (pin "13") (pinfunction "I1_13") (pintype "input"))
    )
    (net (code "241") (name "N$266") (class "Default")
      (node (ref "E20") (pin "1") (pinfunction "I0_1") (pintype "input"))
    )
    (net (code "242") (name "N$267") (class "Default")
      (node (ref "E20") (pin "5") (pinfunction "I1_5") (pintype "input"))
    )
    (net (code "243") (name "N$268") (class "Default")
      (node (ref "E20") (pin "2") (pinfunction "I1_2") (pintype "input"))
    )
    (net (code "244") (name "N$269") (class "Default")
      (node (ref "E20") (pin "9") (pinfunction "I0_9") (pintype "input"))
    )
    (net (code "245") (name "N$270") (class "Default")
      (node (ref "E20") (pin "10") (pinfunction "I1_10") (pintype "input"))
    )
    (net (code "246") (name "N$271") (class "Default")
      (node (ref "E20") (pin "12") (pinfunction "I0_12") (pintype "input"))
    )
    (net (code "247") (name "N$272") (class "Default")
      (node (ref "E20") (pin "4") (pinfunction "I0_4") (pintype "input"))
    )
    (net (code "248") (name "N$274") (class "Default")
      (node (ref "E19") (pin "1") (pinfunction "I0_1") (pintype "input"))
    )
    (net (code "249") (name "N$276") (class "Default")
      (node (ref "E19") (pin "13") (pinfunction "I2_13") (pintype "input"))
    )
    (net (code "250") (name "N$277") (class "Default")
      (node (ref "E19") (pin "9") (pinfunction "I0_9") (pintype "input"))
    )
    (net (code "251") (name "N$278") (class "Default")
      (node (ref "E19") (pin "11") (pinfunction "I2_11") (pintype "input"))
    )
    (net (code "252") (name "N$279") (class "Default")
      (node (ref "E19") (pin "2") (pinfunction "I1_2") (pintype "input"))
    )
    (net (code "253") (name "N$281") (class "Default")
      (node (ref "E19") (pin "10") (pinfunction "I1_10") (pintype "input"))
    )
    (net (code "254") (name "N$282") (class "Default")
      (node (ref "E21") (pin "13") (pinfunction "I3_13") (pintype "input"))
    )
    (net (code "255") (name "N$283") (class "Default")
      (node (ref "E21") (pin "9") (pinfunction "I0_9") (pintype "input"))
    )
    (net (code "256") (name "N$284") (class "Default")
      (node (ref "E21") (pin "2") (pinfunction "I1_2") (pintype "input"))
    )
    (net (code "257") (name "N$285") (class "Default")
      (node (ref "E21") (pin "10") (pinfunction "I1_10") (pintype "input"))
    )
    (net (code "258") (name "N$286") (class "Default")
      (node (ref "E21") (pin "4") (pinfunction "I2_4") (pintype "input"))
    )
    (net (code "259") (name "N$287") (class "Default")
      (node (ref "E21") (pin "5") (pinfunction "I3_5") (pintype "input"))
    )
    (net (code "260") (name "N$288") (class "Default")
      (node (ref "E21") (pin "12") (pinfunction "I2_12") (pintype "input"))
    )
    (net (code "261") (name "N$289") (class "Default")
      (node (ref "E21") (pin "1") (pinfunction "I0_1") (pintype "input"))
    )
    (net (code "262") (name "N$290") (class "Default")
      (node (ref "E3") (pin "11") (pinfunction "Y1_11") (pintype "input"))
    )
    (net (code "263") (name "N$291") (class "Default")
      (node (ref "E3") (pin "1") (pinfunction "Y1_1") (pintype "input"))
    )
    (net (code "264") (name "N$292") (class "Default")
      (node (ref "E3") (pin "13") (pinfunction "Y2_13") (pintype "input"))
    )
    (net (code "265") (name "N$293") (class "Default")
      (node (ref "E3") (pin "5") (pinfunction "Y3_5") (pintype "input"))
    )
    (net (code "266") (name "N$294") (class "Default")
      (node (ref "E3") (pin "7") (pinfunction "FORCE0_7") (pintype "input"))
    )
    (net (code "267") (name "N$295") (class "Default")
      (node (ref "E3") (pin "9") (pinfunction "FORCE0_9") (pintype "input"))
    )
    (net (code "268") (name "N$296") (class "Default")
      (node (ref "E3") (pin "15") (pinfunction "Y3_15") (pintype "input"))
    )
    (net (code "269") (name "N$297") (class "Default")
      (node (ref "E3") (pin "3") (pinfunction "Y2_3") (pintype "input"))
    )
    (net (code "270") (name "N$298") (class "Default")
      (node (ref "E4") (pin "11") (pinfunction "Y1_11") (pintype "input"))
    )
    (net (code "271") (name "N$299") (class "Default")
      (node (ref "E4") (pin "1") (pinfunction "Y1_1") (pintype "input"))
    )
    (net (code "272") (name "N$300") (class "Default")
      (node (ref "E4") (pin "13") (pinfunction "Y2_13") (pintype "input"))
    )
    (net (code "273") (name "N$301") (class "Default")
      (node (ref "E4") (pin "5") (pinfunction "Y3_5") (pintype "input"))
    )
    (net (code "274") (name "N$302") (class "Default")
      (node (ref "E4") (pin "7") (pinfunction "FORCE0_7") (pintype "input"))
    )
    (net (code "275") (name "N$303") (class "Default")
      (node (ref "E4") (pin "9") (pinfunction "FORCE0_9") (pintype "input"))
    )
    (net (code "276") (name "N$304") (class "Default")
      (node (ref "E4") (pin "15") (pinfunction "Y3_15") (pintype "input"))
    )
    (net (code "277") (name "N$305") (class "Default")
      (node (ref "E4") (pin "3") (pinfunction "Y2_3") (pintype "input"))
    )
    (net (code "278") (name "N$306") (class "Default")
      (node (ref "E3") (pin "10") (pinfunction "A1_10") (pintype "output"))
    )
    (net (code "279") (name "N$307") (class "Default")
      (node (ref "E3") (pin "2") (pinfunction "A1_2") (pintype "output"))
    )
    (net (code "280") (name "N$308") (class "Default")
      (node (ref "E3") (pin "12") (pinfunction "A2_12") (pintype "output"))
    )
    (net (code "281") (name "N$309") (class "Default")
      (node (ref "E3") (pin "6") (pinfunction "A3_6") (pintype "output"))
    )
    (net (code "282") (name "N$310") (class "Default")
      (node (ref "E14") (pin "10") (pinfunction "PRE_10") (pintype "input"))
    )
    (net (code "283") (name "N$311") (class "Default")
      (node (ref "E14") (pin "3") (pinfunction "CLK_3") (pintype "input"))
    )
    (net (code "284") (name "N$312") (class "Default")
      (node (ref "E3") (pin "14") (pinfunction "A3_14") (pintype "output"))
    )
    (net (code "285") (name "N$313") (class "Default")
      (node (ref "E3") (pin "4") (pinfunction "A2_4") (pintype "output"))
    )
    (net (code "286") (name "N$314") (class "Default")
      (node (ref "E4") (pin "10") (pinfunction "A1_10") (pintype "output"))
    )
    (net (code "287") (name "N$315") (class "Default")
      (node (ref "E4") (pin "2") (pinfunction "A1_2") (pintype "output"))
    )
    (net (code "288") (name "N$316") (class "Default")
      (node (ref "E4") (pin "12") (pinfunction "A2_12") (pintype "output"))
    )
    (net (code "289") (name "N$317") (class "Default")
      (node (ref "E4") (pin "6") (pinfunction "A3_6") (pintype "output"))
    )
    (net (code "290") (name "N$318") (class "Default")
      (node (ref "E14") (pin "1") (pinfunction "CLR_1") (pintype "input"))
    )
    (net (code "291") (name "N$319") (class "Default")
      (node (ref "E14") (pin "2") (pinfunction "D_2") (pintype "input"))
    )
    (net (code "292") (name "N$320") (class "Default")
      (node (ref "E4") (pin "14") (pinfunction "A3_14") (pintype "output"))
    )
    (net (code "293") (name "N$321") (class "Default")
      (node (ref "E4") (pin "4") (pinfunction "A2_4") (pintype "output"))
    )
    (net (code "294") (name "N$322") (class "Default")
      (node (ref "E14") (pin "4") (pinfunction "PRE_4") (pintype "input"))
    )
    (net (code "295") (name "N$323") (class "Default")
      (node (ref "E14") (pin "11") (pinfunction "CLK_11") (pintype "input"))
    )
    (net (code "296") (name "N$324") (class "Default")
      (node (ref "E14") (pin "13") (pinfunction "CLR_13") (pintype "input"))
    )
    (net (code "297") (name "N$325") (class "Default")
      (node (ref "E14") (pin "12") (pinfunction "D_12") (pintype "input"))
    )
    (net (code "298") (name "N$326") (class "Default")
      (node (ref "E6") (pin "10") (pinfunction "A2_10") (pintype "input"))
    )
    (net (code "299") (name "N$327") (class "Default")
      (node (ref "E6") (pin "1") (pinfunction "A0_1") (pintype "input"))
    )
    (net (code "300") (name "N$328") (class "Default")
      (node (ref "E6") (pin "2") (pinfunction "B0_2") (pintype "input"))
    )
    (net (code "301") (name "N$329") (class "Default")
      (node (ref "E6") (pin "15") (pinfunction "A3_15") (pintype "input"))
    )
    (net (code "302") (name "N$330") (class "Default")
      (node (ref "E6") (pin "6") (pinfunction "A1_6") (pintype "input"))
    )
    (net (code "303") (name "N$331") (class "Default")
      (node (ref "E6") (pin "5") (pinfunction "B1_5") (pintype "input"))
    )
    (net (code "304") (name "N$332") (class "Default")
      (node (ref "E6") (pin "14") (pinfunction "B3_14") (pintype "input"))
    )
    (net (code "305") (name "N$333") (class "Default")
      (node (ref "E6") (pin "11") (pinfunction "B2_11") (pintype "input"))
    )
    (net (code "306") (name "N$334") (class "Default")
      (node (ref "E7") (pin "10") (pinfunction "A2_10") (pintype "input"))
    )
    (net (code "307") (name "N$335") (class "Default")
      (node (ref "E7") (pin "1") (pinfunction "A0_1") (pintype "input"))
    )
    (net (code "308") (name "N$336") (class "Default")
      (node (ref "E7") (pin "2") (pinfunction "B0_2") (pintype "input"))
    )
    (net (code "309") (name "N$337") (class "Default")
      (node (ref "E7") (pin "15") (pinfunction "A3_15") (pintype "input"))
    )
    (net (code "310") (name "N$338") (class "Default")
      (node (ref "E7") (pin "6") (pinfunction "A1_6") (pintype "input"))
    )
    (net (code "311") (name "N$339") (class "Default")
      (node (ref "E7") (pin "5") (pinfunction "B1_5") (pintype "input"))
    )
    (net (code "312") (name "N$340") (class "Default")
      (node (ref "E7") (pin "14") (pinfunction "B3_14") (pintype "input"))
    )
    (net (code "313") (name "N$341") (class "Default")
      (node (ref "E7") (pin "11") (pinfunction "B2_11") (pintype "input"))
    )
    (net (code "314") (name "N$342") (class "Default")
      (node (ref "E10") (pin "1") (pinfunction "M_1") (pintype "input"))
    )
    (net (code "315") (name "N$343") (class "Default")
      (node (ref "E10") (pin "14") (pinfunction "D1_14") (pintype "input"))
    )
    (net (code "316") (name "N$344") (class "Default")
      (node (ref "E10") (pin "13") (pinfunction "D2_13") (pintype "input"))
    )
    (net (code "317") (name "N$345") (class "Default")
      (node (ref "E10") (pin "12") (pinfunction "D3_12") (pintype "input"))
    )
    (net (code "318") (name "N$346") (class "Default")
      (node (ref "E10") (pin "11") (pinfunction "D4_11") (pintype "input"))
    )
    (net (code "319") (name "N$347") (class "Default")
      (node (ref "E10") (pin "9") (pinfunction "G1_9") (pintype "input"))
    )
    (net (code "320") (name "N$348") (class "Default")
      (node (ref "E10") (pin "7") (pinfunction "CLK_7") (pintype "input"))
    )
    (net (code "321") (name "N$349") (class "Default")
      (node (ref "E10") (pin "2") (pinfunction "N_2") (pintype "input"))
    )
    (net (code "322") (name "N$350") (class "Default")
      (node (ref "E11") (pin "1") (pinfunction "M_1") (pintype "input"))
    )
    (net (code "323") (name "N$351") (class "Default")
      (node (ref "E10") (pin "3") (pinfunction "Q1_3") (pintype "tri_state"))
    )
    (net (code "324") (name "N$352") (class "Default")
      (node (ref "E10") (pin "4") (pinfunction "Q2_4") (pintype "tri_state"))
    )
    (net (code "325") (name "N$353") (class "Default")
      (node (ref "E10") (pin "5") (pinfunction "Q3_5") (pintype "tri_state"))
    )
    (net (code "326") (name "N$354") (class "Default")
      (node (ref "E10") (pin "6") (pinfunction "Q4_6") (pintype "tri_state"))
    )
    (net (code "327") (name "N$355") (class "Default")
      (node (ref "E10") (pin "10") (pinfunction "G2_10") (pintype "input"))
    )
    (net (code "328") (name "N$356") (class "Default")
      (node (ref "E10") (pin "15") (pinfunction "CLR_15") (pintype "input"))
    )
    (net (code "329") (name "N$357") (class "Default")
      (node (ref "E11") (pin "14") (pinfunction "D1_14") (pintype "input"))
    )
    (net (code "330") (name "N$358") (class "Default")
      (node (ref "E11") (pin "13") (pinfunction "D2_13") (pintype "input"))
    )
    (net (code "331") (name "N$359") (class "Default")
      (node (ref "E11") (pin "12") (pinfunction "D3_12") (pintype "input"))
    )
    (net (code "332") (name "N$360") (class "Default")
      (node (ref "E11") (pin "11") (pinfunction "D4_11") (pintype "input"))
    )
    (net (code "333") (name "N$361") (class "Default")
      (node (ref "E11") (pin "9") (pinfunction "G1_9") (pintype "input"))
    )
    (net (code "334") (name "N$362") (class "Default")
      (node (ref "E11") (pin "7") (pinfunction "CLK_7") (pintype "input"))
    )
    (net (code "335") (name "N$363") (class "Default")
      (node (ref "E11") (pin "2") (pinfunction "N_2") (pintype "input"))
    )
    (net (code "336") (name "N$364") (class "Default")
      (node (ref "E11") (pin "10") (pinfunction "G2_10") (pintype "input"))
    )
    (net (code "337") (name "N$365") (class "Default")
      (node (ref "E11") (pin "15") (pinfunction "CLR_15") (pintype "input"))
    )
    (net (code "338") (name "N$366") (class "Default")
      (node (ref "E17") (pin "1") (pinfunction "M_1") (pintype "input"))
    )
    (net (code "339") (name "N$367") (class "Default")
      (node (ref "E17") (pin "14") (pinfunction "D1_14") (pintype "input"))
    )
    (net (code "340") (name "N$368") (class "Default")
      (node (ref "E17") (pin "13") (pinfunction "D2_13") (pintype "input"))
    )
    (net (code "341") (name "N$369") (class "Default")
      (node (ref "E17") (pin "12") (pinfunction "D3_12") (pintype "input"))
    )
    (net (code "342") (name "N$370") (class "Default")
      (node (ref "E17") (pin "11") (pinfunction "D4_11") (pintype "input"))
    )
    (net (code "343") (name "N$371") (class "Default")
      (node (ref "E17") (pin "9") (pinfunction "G1_9") (pintype "input"))
    )
    (net (code "344") (name "N$372") (class "Default")
      (node (ref "E17") (pin "7") (pinfunction "CLK_7") (pintype "input"))
    )
    (net (code "345") (name "N$373") (class "Default")
      (node (ref "E17") (pin "2") (pinfunction "N_2") (pintype "input"))
    )
    (net (code "346") (name "N$374") (class "Default")
      (node (ref "E17") (pin "10") (pinfunction "G2_10") (pintype "input"))
    )
    (net (code "347") (name "N$375") (class "Default")
      (node (ref "E17") (pin "15") (pinfunction "CLR_15") (pintype "input"))
    )
    (net (code "348") (name "N$376") (class "Default")
      (node (ref "E18") (pin "1") (pinfunction "M_1") (pintype "input"))
    )
    (net (code "349") (name "N$377") (class "Default")
      (node (ref "E18") (pin "14") (pinfunction "D1_14") (pintype "input"))
    )
    (net (code "350") (name "N$378") (class "Default")
      (node (ref "E18") (pin "13") (pinfunction "D2_13") (pintype "input"))
    )
    (net (code "351") (name "N$379") (class "Default")
      (node (ref "E18") (pin "12") (pinfunction "D3_12") (pintype "input"))
    )
    (net (code "352") (name "N$380") (class "Default")
      (node (ref "E18") (pin "11") (pinfunction "D4_11") (pintype "input"))
    )
    (net (code "353") (name "N$381") (class "Default")
      (node (ref "E18") (pin "9") (pinfunction "G1_9") (pintype "input"))
    )
    (net (code "354") (name "N$382") (class "Default")
      (node (ref "E18") (pin "7") (pinfunction "CLK_7") (pintype "input"))
    )
    (net (code "355") (name "N$383") (class "Default")
      (node (ref "E18") (pin "2") (pinfunction "N_2") (pintype "input"))
    )
    (net (code "356") (name "N$384") (class "Default")
      (node (ref "E18") (pin "10") (pinfunction "G2_10") (pintype "input"))
    )
    (net (code "357") (name "N$385") (class "Default")
      (node (ref "E18") (pin "15") (pinfunction "CLR_15") (pintype "input"))
    )
    (net (code "358") (name "N$386") (class "Default")
      (node (ref "E11") (pin "3") (pinfunction "Q1_3") (pintype "tri_state"))
    )
    (net (code "359") (name "N$387") (class "Default")
      (node (ref "E11") (pin "4") (pinfunction "Q2_4") (pintype "tri_state"))
    )
    (net (code "360") (name "N$388") (class "Default")
      (node (ref "E11") (pin "5") (pinfunction "Q3_5") (pintype "tri_state"))
    )
    (net (code "361") (name "N$389") (class "Default")
      (node (ref "E11") (pin "6") (pinfunction "Q4_6") (pintype "tri_state"))
    )
    (net (code "362") (name "N$390") (class "Default")
      (node (ref "E6") (pin "3") (pinfunction "F0_3") (pintype "open_collector"))
    )
    (net (code "363") (name "N$391") (class "Default")
      (node (ref "E6") (pin "13") (pinfunction "F3_13") (pintype "open_collector"))
    )
    (net (code "364") (name "N$392") (class "Default")
      (node (ref "E6") (pin "4") (pinfunction "F1_4") (pintype "open_collector"))
    )
    (net (code "365") (name "N$393") (class "Default")
      (node (ref "E6") (pin "12") (pinfunction "F2_12") (pintype "open_collector"))
    )
    (net (code "366") (name "N$394") (class "Default")
      (node (ref "E7") (pin "3") (pinfunction "F0_3") (pintype "open_collector"))
    )
    (net (code "367") (name "N$395") (class "Default")
      (node (ref "E7") (pin "4") (pinfunction "F1_4") (pintype "open_collector"))
    )
    (net (code "368") (name "N$396") (class "Default")
      (node (ref "E7") (pin "12") (pinfunction "F2_12") (pintype "open_collector"))
    )
    (net (code "369") (name "N$397") (class "Default")
      (node (ref "E7") (pin "13") (pinfunction "F3_13") (pintype "open_collector"))
    )
    (net (code "370") (name "N$398") (class "Default")
      (node (ref "E6") (pin "7") (pinfunction "S1_7") (pintype "input"))
    )
    (net (code "371") (name "N$399") (class "Default")
      (node (ref "E6") (pin "9") (pinfunction "S0_9") (pintype "input"))
    )
    (net (code "372") (name "N$400") (class "Default")
      (node (ref "E7") (pin "7") (pinfunction "S1_7") (pintype "input"))
    )
    (net (code "373") (name "N$401") (class "Default")
      (node (ref "E7") (pin "9") (pinfunction "S0_9") (pintype "input"))
    )
    (net (code "374") (name "N$418") (class "Default")
      (node (ref "E9") (pin "3") (pinfunction "O2_3") (pintype "output"))
    )
    (net (code "375") (name "N$419") (class "Default")
      (node (ref "E9") (pin "15") (pinfunction "A_15") (pintype "input"))
    )
    (net (code "376") (name "N$420") (class "Default")
      (node (ref "E9") (pin "14") (pinfunction "B_14") (pintype "input"))
    )
    (net (code "377") (name "N$421") (class "Default")
      (node (ref "E9") (pin "13") (pinfunction "C_13") (pintype "input"))
    )
    (net (code "378") (name "N$422") (class "Default")
      (node (ref "E9") (pin "12") (pinfunction "D_12") (pintype "input"))
    )
    (net (code "379") (name "N$423") (class "Default")
      (node (ref "E9") (pin "1") (pinfunction "O0_1") (pintype "output"))
    )
    (net (code "380") (name "N$424") (class "Default")
      (node (ref "E9") (pin "2") (pinfunction "O1_2") (pintype "output"))
    )
    (net (code "381") (name "N$425") (class "Default")
      (node (ref "E9") (pin "4") (pinfunction "O3_4") (pintype "output"))
    )
    (net (code "382") (name "N$426") (class "Default")
      (node (ref "E12") (pin "3") (pinfunction "O2_3") (pintype "output"))
    )
    (net (code "383") (name "N$427") (class "Default")
      (node (ref "E9") (pin "5") (pinfunction "O4_5") (pintype "output"))
    )
    (net (code "384") (name "N$428") (class "Default")
      (node (ref "E9") (pin "6") (pinfunction "O5_6") (pintype "output"))
    )
    (net (code "385") (name "N$429") (class "Default")
      (node (ref "E9") (pin "7") (pinfunction "O6_7") (pintype "output"))
    )
    (net (code "386") (name "N$430") (class "Default")
      (node (ref "E9") (pin "9") (pinfunction "O7_9") (pintype "output"))
    )
    (net (code "387") (name "N$431") (class "Default")
      (node (ref "E9") (pin "10") (pinfunction "O8_10") (pintype "output"))
    )
    (net (code "388") (name "N$432") (class "Default")
      (node (ref "E9") (pin "11") (pinfunction "O9_11") (pintype "output"))
    )
    (net (code "389") (name "N$433") (class "Default")
      (node (ref "E12") (pin "1") (pinfunction "O0_1") (pintype "output"))
    )
    (net (code "390") (name "N$434") (class "Default")
      (node (ref "E12") (pin "2") (pinfunction "O1_2") (pintype "output"))
    )
    (net (code "391") (name "N$435") (class "Default")
      (node (ref "E12") (pin "4") (pinfunction "O3_4") (pintype "output"))
    )
    (net (code "392") (name "N$436") (class "Default")
      (node (ref "E12") (pin "5") (pinfunction "O4_5") (pintype "output"))
    )
    (net (code "393") (name "N$437") (class "Default")
      (node (ref "E12") (pin "6") (pinfunction "O5_6") (pintype "output"))
    )
    (net (code "394") (name "N$438") (class "Default")
      (node (ref "E12") (pin "7") (pinfunction "O6_7") (pintype "output"))
    )
    (net (code "395") (name "N$439") (class "Default")
      (node (ref "E12") (pin "9") (pinfunction "O7_9") (pintype "output"))
    )
    (net (code "396") (name "N$440") (class "Default")
      (node (ref "E12") (pin "10") (pinfunction "O8_10") (pintype "output"))
    )
    (net (code "397") (name "N$441") (class "Default")
      (node (ref "E12") (pin "11") (pinfunction "O9_11") (pintype "output"))
    )
    (net (code "398") (name "N$442") (class "Default")
      (node (ref "E12") (pin "15") (pinfunction "A_15") (pintype "input"))
    )
    (net (code "399") (name "N$443") (class "Default")
      (node (ref "E12") (pin "14") (pinfunction "B_14") (pintype "input"))
    )
    (net (code "400") (name "N$444") (class "Default")
      (node (ref "E12") (pin "13") (pinfunction "C_13") (pintype "input"))
    )
    (net (code "401") (name "N$445") (class "Default")
      (node (ref "E12") (pin "12") (pinfunction "D_12") (pintype "input"))
    )
    (net (code "402") (name "N$446") (class "Default")
      (node (ref "E14") (pin "8") (pinfunction "~{Q}_8") (pintype "output"))
    )
    (net (code "403") (name "N$447") (class "Default")
      (node (ref "E14") (pin "6") (pinfunction "~{Q}_6") (pintype "output"))
    )
    (net (code "404") (name "N$448") (class "Default")
      (node (ref "E14") (pin "9") (pinfunction "Q_9") (pintype "output"))
    )
    (net (code "405") (name "N$449") (class "Default")
      (node (ref "E14") (pin "5") (pinfunction "Q_5") (pintype "output"))
    )
    (net (code "406") (name "N$450") (class "Default")
      (node (ref "E16") (pin "11") (pinfunction "O_11") (pintype "output"))
    )
    (net (code "407") (name "N$451") (class "Default")
      (node (ref "E15") (pin "3") (pinfunction "O_3") (pintype "output"))
    )
    (net (code "408") (name "N$453") (class "Default")
      (node (ref "E16") (pin "3") (pinfunction "O_3") (pintype "output"))
    )
    (net (code "409") (name "N$454") (class "Default")
      (node (ref "E15") (pin "14") (pinfunction "O_14") (pintype "output"))
    )
    (net (code "410") (name "N$456") (class "Default")
      (node (ref "E15") (pin "13") (pinfunction "O_13") (pintype "output"))
    )
    (net (code "411") (name "N$457") (class "Default")
      (node (ref "E15") (pin "2") (pinfunction "O_2") (pintype "output"))
    )
    (net (code "412") (name "N$459") (class "Default")
      (node (ref "E19") (pin "12") (pinfunction "O_12") (pintype "output"))
    )
    (net (code "413") (name "N$460") (class "Default")
      (node (ref "E19") (pin "8") (pinfunction "O_8") (pintype "output"))
    )
    (net (code "414") (name "N$461") (class "Default")
      (node (ref "E17") (pin "3") (pinfunction "Q1_3") (pintype "tri_state"))
    )
    (net (code "415") (name "N$462") (class "Default")
      (node (ref "E17") (pin "4") (pinfunction "Q2_4") (pintype "tri_state"))
    )
    (net (code "416") (name "N$463") (class "Default")
      (node (ref "E17") (pin "5") (pinfunction "Q3_5") (pintype "tri_state"))
    )
    (net (code "417") (name "N$464") (class "Default")
      (node (ref "E17") (pin "6") (pinfunction "Q4_6") (pintype "tri_state"))
    )
    (net (code "418") (name "N$465") (class "Default")
      (node (ref "E18") (pin "3") (pinfunction "Q1_3") (pintype "tri_state"))
    )
    (net (code "419") (name "N$466") (class "Default")
      (node (ref "E18") (pin "4") (pinfunction "Q2_4") (pintype "tri_state"))
    )
    (net (code "420") (name "N$467") (class "Default")
      (node (ref "E18") (pin "5") (pinfunction "Q3_5") (pintype "tri_state"))
    )
    (net (code "421") (name "N$468") (class "Default")
      (node (ref "E18") (pin "6") (pinfunction "Q4_6") (pintype "tri_state"))
    )
    (net (code "422") (name "N$469") (class "Default")
      (node (ref "E20") (pin "6") (pinfunction "O_6") (pintype "output"))
    )
    (net (code "423") (name "N$470") (class "Default")
      (node (ref "E20") (pin "3") (pinfunction "O_3") (pintype "output"))
    )
    (net (code "424") (name "N$471") (class "Default")
      (node (ref "E20") (pin "8") (pinfunction "O_8") (pintype "output"))
    )
    (net (code "425") (name "N$472") (class "Default")
      (node (ref "E21") (pin "6") (pinfunction "O_6") (pintype "open_collector"))
    )
    (net (code "426") (name "N$473") (class "Default")
      (node (ref "E20") (pin "11") (pinfunction "O_11") (pintype "output"))
    )
    (net (code "427") (name "N$474") (class "Default")
      (node (ref "E21") (pin "8") (pinfunction "O_8") (pintype "open_collector"))
    )
    (net (code "428") (name "N$476") (class "Default")
      (node (ref "E22") (pin "2") (pinfunction "SR_2") (pintype "input"))
    )
    (net (code "429") (name "N$477") (class "Default")
      (node (ref "E22") (pin "3") (pinfunction "A_3") (pintype "input"))
    )
    (net (code "430") (name "N$478") (class "Default")
      (node (ref "E22") (pin "4") (pinfunction "B_4") (pintype "input"))
    )
    (net (code "431") (name "N$479") (class "Default")
      (node (ref "E22") (pin "5") (pinfunction "C_5") (pintype "input"))
    )
    (net (code "432") (name "N$480") (class "Default")
      (node (ref "E22") (pin "6") (pinfunction "D_6") (pintype "input"))
    )
    (net (code "433") (name "N$481") (class "Default")
      (node (ref "E22") (pin "7") (pinfunction "SL_7") (pintype "input"))
    )
    (net (code "434") (name "N$482") (class "Default")
      (node (ref "E22") (pin "11") (pinfunction "CLK_11") (pintype "input"))
    )
    (net (code "435") (name "N$483") (class "Default")
      (node (ref "E22") (pin "1") (pinfunction "CLR_1") (pintype "input"))
    )
    (net (code "436") (name "N$484") (class "Default")
      (node (ref "E22") (pin "15") (pinfunction "QA_15") (pintype "output"))
    )
    (net (code "437") (name "N$485") (class "Default")
      (node (ref "E22") (pin "14") (pinfunction "QB_14") (pintype "output"))
    )
    (net (code "438") (name "N$486") (class "Default")
      (node (ref "E22") (pin "13") (pinfunction "QC_13") (pintype "output"))
    )
    (net (code "439") (name "N$487") (class "Default")
      (node (ref "E22") (pin "12") (pinfunction "QD_12") (pintype "output"))
    )
    (net (code "440") (name "N$488") (class "Default")
      (node (ref "E22") (pin "9") (pinfunction "S0_9") (pintype "input"))
    )
    (net (code "441") (name "N$489") (class "Default")
      (node (ref "E22") (pin "10") (pinfunction "S1_10") (pintype "input"))
    )
    (net (code "442") (name "N$490") (class "Default")
      (node (ref "E26") (pin "23") (pinfunction "VCC3_23") (pintype "input"))
    )
    (net (code "443") (name "N$491") (class "Default")
      (node (ref "E27") (pin "23") (pinfunction "VCC3_23") (pintype "input"))
    )
    (net (code "444") (name "N$493") (class "Default")
      (node (ref "E26") (pin "15") (pinfunction "VBB_15") (pintype "input"))
    )
    (net (code "445") (name "N$494") (class "Default")
      (node (ref "E27") (pin "15") (pinfunction "VBB_15") (pintype "input"))
    )
    (net (code "446") (name "N$497") (class "Default")
      (node (ref "E28") (pin "23") (pinfunction "VCC3_23") (pintype "input"))
    )
    (net (code "447") (name "N$498") (class "Default")
      (node (ref "E28") (pin "15") (pinfunction "VBB_15") (pintype "input"))
    )
    (net (code "448") (name "N$499") (class "Default")
      (node (ref "R5") (pin "1") (pinfunction "1_1") (pintype "passive"))
    )
    (net (code "449") (name "N$500") (class "Default")
      (node (ref "R1") (pin "1") (pinfunction "1_1") (pintype "passive"))
    )
    (net (code "450") (name "N$501") (class "Default")
      (node (ref "R2") (pin "1") (pinfunction "1_1") (pintype "passive"))
    )
    (net (code "451") (name "N$502") (class "Default")
      (node (ref "R3") (pin "1") (pinfunction "1_1") (pintype "passive"))
    )
    (net (code "452") (name "N$503") (class "Default")
      (node (ref "R4") (pin "1") (pinfunction "1_1") (pintype "passive"))
    )
    (net (code "453") (name "N$504") (class "Default")
      (node (ref "R6") (pin "1") (pinfunction "1_1") (pintype "passive"))
    )
    (net (code "454") (name "N$505") (class "Default")
      (node (ref "R5") (pin "2") (pinfunction "2_2") (pintype "passive"))
    )
    (net (code "455") (name "N$506") (class "Default")
      (node (ref "R1") (pin "2") (pinfunction "2_2") (pintype "passive"))
    )
    (net (code "456") (name "N$507") (class "Default")
      (node (ref "R2") (pin "2") (pinfunction "2_2") (pintype "passive"))
    )
    (net (code "457") (name "N$508") (class "Default")
      (node (ref "R3") (pin "2") (pinfunction "2_2") (pintype "passive"))
    )
    (net (code "458") (name "N$509") (class "Default")
      (node (ref "R4") (pin "2") (pinfunction "2_2") (pintype "passive"))
    )
    (net (code "459") (name "N$510") (class "Default")
      (node (ref "R6") (pin "2") (pinfunction "2_2") (pintype "passive"))
    )
    (net (code "460") (name "N$511") (class "Default")
      (node (ref "R7") (pin "1") (pinfunction "1_1") (pintype "passive"))
    )
    (net (code "461") (name "N$512") (class "Default")
      (node (ref "R7") (pin "2") (pinfunction "2_2") (pintype "passive"))
    )
    (net (code "462") (name "N$513") (class "Default")
      (node (ref "R8") (pin "1") (pinfunction "1_1") (pintype "passive"))
    )
    (net (code "463") (name "N$514") (class "Default")
      (node (ref "R8") (pin "2") (pinfunction "2_2") (pintype "passive"))
    )
    (net (code "464") (name "N$515") (class "Default")
      (node (ref "R10") (pin "1") (pinfunction "1_1") (pintype "passive"))
    )
    (net (code "465") (name "N$516") (class "Default")
      (node (ref "R10") (pin "2") (pinfunction "2_2") (pintype "passive"))
    )
    (net (code "466") (name "N$517") (class "Default")
      (node (ref "R9") (pin "1") (pinfunction "1_1") (pintype "passive"))
    )
    (net (code "467") (name "N$518") (class "Default")
      (node (ref "R11") (pin "1") (pinfunction "1_1") (pintype "passive"))
    )
    (net (code "468") (name "N$519") (class "Default")
      (node (ref "R11") (pin "2") (pinfunction "2_2") (pintype "passive"))
    )
    (net (code "469") (name "N$520") (class "Default")
      (node (ref "R9") (pin "2") (pinfunction "2_2") (pintype "passive"))
    )
    (net (code "470") (name "N$521") (class "Default")
      (node (ref "R12") (pin "1") (pinfunction "1_1") (pintype "passive"))
    )
    (net (code "471") (name "N$522") (class "Default")
      (node (ref "R18") (pin "2") (pinfunction "2_2") (pintype "passive"))
    )
    (net (code "472") (name "N$523") (class "Default")
      (node (ref "R12") (pin "2") (pinfunction "2_2") (pintype "passive"))
    )
    (net (code "473") (name "N$524") (class "Default")
      (node (ref "R13") (pin "2") (pinfunction "2_2") (pintype "passive"))
    )
    (net (code "474") (name "N$525") (class "Default")
      (node (ref "R14") (pin "2") (pinfunction "2_2") (pintype "passive"))
    )
    (net (code "475") (name "N$526") (class "Default")
      (node (ref "R15") (pin "2") (pinfunction "2_2") (pintype "passive"))
    )
    (net (code "476") (name "N$527") (class "Default")
      (node (ref "R16") (pin "2") (pinfunction "2_2") (pintype "passive"))
    )
    (net (code "477") (name "N$528") (class "Default")
      (node (ref "R17") (pin "2") (pinfunction "2_2") (pintype "passive"))
    )
    (net (code "478") (name "N$529") (class "Default")
      (node (ref "R19") (pin "2") (pinfunction "2_2") (pintype "passive"))
    )
    (net (code "479") (name "N$530") (class "Default")
      (node (ref "R19") (pin "1") (pinfunction "1_1") (pintype "passive"))
    )
    (net (code "480") (name "N$531") (class "Default")
      (node (ref "R18") (pin "1") (pinfunction "1_1") (pintype "passive"))
    )
    (net (code "481") (name "N$532") (class "Default")
      (node (ref "R17") (pin "1") (pinfunction "1_1") (pintype "passive"))
    )
    (net (code "482") (name "N$533") (class "Default")
      (node (ref "R16") (pin "1") (pinfunction "1_1") (pintype "passive"))
    )
    (net (code "483") (name "N$534") (class "Default")
      (node (ref "R15") (pin "1") (pinfunction "1_1") (pintype "passive"))
    )
    (net (code "484") (name "N$535") (class "Default")
      (node (ref "R14") (pin "1") (pinfunction "1_1") (pintype "passive"))
    )
    (net (code "485") (name "N$536") (class "Default")
      (node (ref "R13") (pin "1") (pinfunction "1_1") (pintype "passive"))
    )
    (net (code "486") (name "N$537") (class "Default")
      (node (ref "R20") (pin "1") (pinfunction "1_1") (pintype "passive"))
    )
    (net (code "487") (name "N$538") (class "Default")
      (node (ref "R20") (pin "2") (pinfunction "2_2") (pintype "passive"))
    )
    (net (code "488") (name "N$539") (class "Default")
      (node (ref "R21") (pin "1") (pinfunction "1_1") (pintype "passive"))
    )
    (net (code "489") (name "N$540") (class "Default")
      (node (ref "R24") (pin "2") (pinfunction "2_2") (pintype "passive"))
    )
    (net (code "490") (name "N$541") (class "Default")
      (node (ref "R21") (pin "2") (pinfunction "2_2") (pintype "passive"))
    )
    (net (code "491") (name "N$542") (class "Default")
      (node (ref "R22") (pin "2") (pinfunction "2_2") (pintype "passive"))
    )
    (net (code "492") (name "N$543") (class "Default")
      (node (ref "R23") (pin "2") (pinfunction "2_2") (pintype "passive"))
    )
    (net (code "493") (name "N$544") (class "Default")
      (node (ref "R25") (pin "2") (pinfunction "2_2") (pintype "passive"))
    )
    (net (code "494") (name "N$545") (class "Default")
      (node (ref "R25") (pin "1") (pinfunction "1_1") (pintype "passive"))
    )
    (net (code "495") (name "N$546") (class "Default")
      (node (ref "R24") (pin "1") (pinfunction "1_1") (pintype "passive"))
    )
    (net (code "496") (name "N$547") (class "Default")
      (node (ref "R23") (pin "1") (pinfunction "1_1") (pintype "passive"))
    )
    (net (code "497") (name "N$548") (class "Default")
      (node (ref "R22") (pin "1") (pinfunction "1_1") (pintype "passive"))
    )
    (net (code "498") (name "N$549") (class "Default")
      (node (ref "W1") (pin "1") (pinfunction "1_1") (pintype "passive"))
    )
    (net (code "499") (name "N$551") (class "Default")
      (node (ref "W4") (pin "1") (pinfunction "1_1") (pintype "passive"))
    )
    (net (code "500") (name "N$552") (class "Default")
      (node (ref "W2") (pin "1") (pinfunction "1_1") (pintype "passive"))
    )
    (net (code "501") (name "N$554") (class "Default")
      (node (ref "W1") (pin "2") (pinfunction "2_2") (pintype "passive"))
    )
    (net (code "502") (name "N$555") (class "Default")
      (node (ref "W4") (pin "2") (pinfunction "2_2") (pintype "passive"))
    )
    (net (code "503") (name "N$556") (class "Default")
      (node (ref "W2") (pin "2") (pinfunction "2_2") (pintype "passive"))
    )
    (net (code "504") (name "N$557") (class "Default")
      (node (ref "R30") (pin "1") (pinfunction "1_1") (pintype "passive"))
    )
    (net (code "505") (name "N$558") (class "Default")
      (node (ref "R30") (pin "2") (pinfunction "2_2") (pintype "passive"))
    )
    (net (code "506") (name "N$559") (class "Default")
      (node (ref "D1") (pin "A") (pinfunction "A_A") (pintype "passive"))
    )
    (net (code "507") (name "N$560") (class "Default")
      (node (ref "D1") (pin "C") (pinfunction "C_C") (pintype "passive"))
    )
    (net (code "508") (name "N$561") (class "Default")
      (node (ref "R32") (pin "1") (pinfunction "1_1") (pintype "passive"))
    )
    (net (code "509") (name "N$562") (class "Default")
      (node (ref "R32") (pin "2") (pinfunction "2_2") (pintype "passive"))
    )
    (net (code "510") (name "N$563") (class "Default")
      (node (ref "R33") (pin "1") (pinfunction "1_1") (pintype "passive"))
    )
    (net (code "511") (name "N$564") (class "Default")
      (node (ref "R33") (pin "2") (pinfunction "2_2") (pintype "passive"))
    )
    (net (code "512") (name "N$565") (class "Default")
      (node (ref "C29") (pin "1") (pinfunction "1_1") (pintype "passive"))
    )
    (net (code "513") (name "N$566") (class "Default")
      (node (ref "C29") (pin "2") (pinfunction "2_2") (pintype "passive"))
    )
    (net (code "514") (name "N$567") (class "Default")
      (node (ref "C30") (pin "1") (pinfunction "1_1") (pintype "passive"))
    )
    (net (code "515") (name "N$568") (class "Default")
      (node (ref "C30") (pin "2") (pinfunction "2_2") (pintype "passive"))
    )
    (net (code "516") (name "N$569") (class "Default")
      (node (ref "R31") (pin "1") (pinfunction "1_1") (pintype "passive"))
    )
    (net (code "517") (name "N$570") (class "Default")
      (node (ref "R31") (pin "2") (pinfunction "2_2") (pintype "passive"))
    )
    (net (code "518") (name "Net-(E8-Pad1)") (class "Default")
      (node (ref "E8") (pin "1") (pinfunction "1_1") (pintype "passive"))
      (node (ref "SV3") (pin "1") (pinfunction "1_1") (pintype "passive"))
    )
    (net (code "519") (name "Net-(E8-Pad2)") (class "Default")
      (node (ref "E8") (pin "2") (pinfunction "2_2") (pintype "passive"))
      (node (ref "SV3") (pin "2") (pinfunction "2_2") (pintype "passive"))
    )
    (net (code "520") (name "Net-(E8-Pad3)") (class "Default")
      (node (ref "E8") (pin "3") (pinfunction "3_3") (pintype "passive"))
      (node (ref "SV3") (pin "3") (pinfunction "3_3") (pintype "passive"))
    )
    (net (code "521") (name "Net-(E8-Pad4)") (class "Default")
      (node (ref "E8") (pin "4") (pinfunction "4_4") (pintype "passive"))
      (node (ref "SV3") (pin "4") (pinfunction "4_4") (pintype "passive"))
    )
    (net (code "522") (name "Net-(E8-Pad5)") (class "Default")
      (node (ref "E8") (pin "5") (pinfunction "5_5") (pintype "passive"))
      (node (ref "SV3") (pin "5") (pinfunction "5_5") (pintype "passive"))
    )
    (net (code "523") (name "Net-(E8-Pad6)") (class "Default")
      (node (ref "E8") (pin "6") (pinfunction "6_6") (pintype "passive"))
      (node (ref "SV3") (pin "6") (pinfunction "6_6") (pintype "passive"))
    )
    (net (code "524") (name "Net-(E8-Pad7)") (class "Default")
      (node (ref "E8") (pin "7") (pinfunction "7_7") (pintype "passive"))
      (node (ref "SV3") (pin "7") (pinfunction "7_7") (pintype "passive"))
    )
    (net (code "525") (name "Net-(E8-Pad8)") (class "Default")
      (node (ref "E8") (pin "8") (pinfunction "8_8") (pintype "passive"))
      (node (ref "SV3") (pin "8") (pinfunction "8_8") (pintype "passive"))
    )
    (net (code "526") (name "Net-(E8-Pad9)") (class "Default")
      (node (ref "E8") (pin "9") (pinfunction "9_9") (pintype "passive"))
      (node (ref "SV2") (pin "1") (pinfunction "1_1") (pintype "passive"))
    )
    (net (code "527") (name "Net-(E8-Pad10)") (class "Default")
      (node (ref "E8") (pin "10") (pinfunction "10_10") (pintype "passive"))
      (node (ref "SV2") (pin "2") (pinfunction "2_2") (pintype "passive"))
    )
    (net (code "528") (name "Net-(E8-Pad11)") (class "Default")
      (node (ref "E8") (pin "11") (pinfunction "11_11") (pintype "passive"))
      (node (ref "SV2") (pin "3") (pinfunction "3_3") (pintype "passive"))
    )
    (net (code "529") (name "Net-(E8-Pad12)") (class "Default")
      (node (ref "E8") (pin "12") (pinfunction "12_12") (pintype "passive"))
      (node (ref "SV2") (pin "4") (pinfunction "4_4") (pintype "passive"))
    )
    (net (code "530") (name "Net-(E8-Pad13)") (class "Default")
      (node (ref "E8") (pin "13") (pinfunction "13_13") (pintype "passive"))
      (node (ref "SV2") (pin "5") (pinfunction "5_5") (pintype "passive"))
    )
    (net (code "531") (name "Net-(E8-Pad14)") (class "Default")
      (node (ref "E8") (pin "14") (pinfunction "14_14") (pintype "passive"))
      (node (ref "SV2") (pin "6") (pinfunction "6_6") (pintype "passive"))
    )
    (net (code "532") (name "Net-(E8-Pad15)") (class "Default")
      (node (ref "E8") (pin "15") (pinfunction "15_15") (pintype "passive"))
      (node (ref "SV2") (pin "7") (pinfunction "7_7") (pintype "passive"))
    )
    (net (code "533") (name "Net-(E8-Pad16)") (class "Default")
      (node (ref "E8") (pin "16") (pinfunction "16_16") (pintype "passive"))
      (node (ref "SV2") (pin "8") (pinfunction "8_8") (pintype "passive"))
    )
    (net (code "534") (name "Net-(E16B-I0)") (class "Default")
      (node (ref "E16") (pin "4") (pinfunction "I0_4") (pintype "input"))
      (node (ref "SV4") (pin "1") (pinfunction "1_1") (pintype "passive"))
    )
    (net (code "535") (name "Net-(E16B-I1)") (class "Default")
      (node (ref "E16") (pin "5") (pinfunction "I1_5") (pintype "input"))
      (node (ref "SV4") (pin "2") (pinfunction "2_2") (pintype "passive"))
    )
    (net (code "536") (name "Net-(E16B-O)") (class "Default")
      (node (ref "E16") (pin "6") (pinfunction "O_6") (pintype "output"))
      (node (ref "SV4") (pin "3") (pinfunction "3_3") (pintype "passive"))
    )
    (net (code "537") (name "Net-(E16C-I0)") (class "Default")
      (node (ref "E16") (pin "9") (pinfunction "I0_9") (pintype "input"))
      (node (ref "SV5") (pin "2") (pinfunction "2_2") (pintype "passive"))
    )
    (net (code "538") (name "Net-(E16C-I1)") (class "Default")
      (node (ref "E16") (pin "10") (pinfunction "I1_10") (pintype "input"))
      (node (ref "SV5") (pin "3") (pinfunction "3_3") (pintype "passive"))
    )
    (net (code "539") (name "Net-(E16C-O)") (class "Default")
      (node (ref "E16") (pin "8") (pinfunction "O_8") (pintype "output"))
      (node (ref "SV5") (pin "1") (pinfunction "1_1") (pintype "passive"))
    )
    (net (code "540") (name "Net-(E19B-I0)") (class "Default")
      (node (ref "E19") (pin "3") (pinfunction "I0_3") (pintype "input"))
      (node (ref "SV1") (pin "1") (pinfunction "1_1") (pintype "passive"))
    )
    (net (code "541") (name "Net-(E19B-I1)") (class "Default")
      (node (ref "E19") (pin "4") (pinfunction "I1_4") (pintype "input"))
      (node (ref "SV1") (pin "2") (pinfunction "2_2") (pintype "passive"))
    )
    (net (code "542") (name "Net-(E19B-I2)") (class "Default")
      (node (ref "E19") (pin "5") (pinfunction "I2_5") (pintype "input"))
      (node (ref "SV1") (pin "3") (pinfunction "3_3") (pintype "passive"))
    )
    (net (code "543") (name "Net-(E19B-O)") (class "Default")
      (node (ref "E19") (pin "6") (pinfunction "O_6") (pintype "output"))
      (node (ref "SV1") (pin "4") (pinfunction "4_4") (pintype "passive"))
    )
    (net (code "544") (name "Net-(J1-Pad1)") (class "Default")
      (node (ref "J1") (pin "1") (pinfunction "1_1") (pintype "passive"))
      (node (ref "J2") (pin "2") (pinfunction "2_2") (pintype "passive"))
    )
    (net (code "545") (name "Net-(J1-Pad2)") (class "Default")
      (node (ref "J1") (pin "2") (pinfunction "2_2") (pintype "passive"))
      (node (ref "J2") (pin "1") (pinfunction "1_1") (pintype "passive"))
    )
    (net (code "546") (name "O0") (class "Default")
      (node (ref "E24") (pin "4") (pinfunction "O0_4") (pintype "tri_state"))
      (node (ref "E25") (pin "4") (pinfunction "O0_4") (pintype "tri_state"))
    )
    (net (code "547") (name "O1") (class "Default")
      (node (ref "E24") (pin "5") (pinfunction "O1_5") (pintype "tri_state"))
      (node (ref "E25") (pin "5") (pinfunction "O1_5") (pintype "tri_state"))
    )
    (net (code "548") (name "O2") (class "Default")
      (node (ref "E24") (pin "6") (pinfunction "O2_6") (pintype "tri_state"))
      (node (ref "E25") (pin "6") (pinfunction "O2_6") (pintype "tri_state"))
    )
    (net (code "549") (name "O3") (class "Default")
      (node (ref "E24") (pin "7") (pinfunction "O3_7") (pintype "tri_state"))
      (node (ref "E25") (pin "7") (pinfunction "O3_7") (pintype "tri_state"))
    )
    (net (code "550") (name "O4") (class "Default")
      (node (ref "E24") (pin "8") (pinfunction "O4_8") (pintype "tri_state"))
      (node (ref "E25") (pin "8") (pinfunction "O4_8") (pintype "tri_state"))
    )
    (net (code "551") (name "O5") (class "Default")
      (node (ref "E24") (pin "9") (pinfunction "O5_9") (pintype "tri_state"))
      (node (ref "E25") (pin "9") (pinfunction "O5_9") (pintype "tri_state"))
    )
    (net (code "552") (name "O6") (class "Default")
      (node (ref "E24") (pin "10") (pinfunction "O6_10") (pintype "tri_state"))
      (node (ref "E25") (pin "10") (pinfunction "O6_10") (pintype "tri_state"))
    )
    (net (code "553") (name "O7") (class "Default")
      (node (ref "E24") (pin "11") (pinfunction "O7_11") (pintype "tri_state"))
      (node (ref "E25") (pin "11") (pinfunction "O7_11") (pintype "tri_state"))
    )
    (net (code "554") (name "P") (class "Default")
      (node (ref "E24") (pin "13") (pinfunction "P_13") (pintype "input"))
    )
    (net (code "555") (name "VBB") (class "Default")
      (node (ref "E24") (pin "15") (pinfunction "VBB_15") (pintype "input"))
      (node (ref "E25") (pin "15") (pinfunction "VBB_15") (pintype "input"))
    )
    (net (code "556") (name "VCC") (class "Default")
      (node (ref "C1") (pin "1") (pinfunction "1_1") (pintype "passive"))
      (node (ref "C10") (pin "1") (pinfunction "1_1") (pintype "passive"))
      (node (ref "C11") (pin "1") (pinfunction "1_1") (pintype "passive"))
      (node (ref "C12") (pin "1") (pinfunction "1_1") (pintype "passive"))
      (node (ref "C13") (pin "1") (pinfunction "1_1") (pintype "passive"))
      (node (ref "C14") (pin "1") (pinfunction "1_1") (pintype "passive"))
      (node (ref "C15") (pin "1") (pinfunction "1_1") (pintype "passive"))
      (node (ref "C16") (pin "1") (pinfunction "1_1") (pintype "passive"))
      (node (ref "C17") (pin "1") (pinfunction "1_1") (pintype "passive"))
      (node (ref "C18") (pin "1") (pinfunction "1_1") (pintype "passive"))
      (node (ref "C19") (pin "1") (pinfunction "1_1") (pintype "passive"))
      (node (ref "C2") (pin "1") (pinfunction "1_1") (pintype "passive"))
      (node (ref "C20") (pin "1") (pinfunction "1_1") (pintype "passive"))
      (node (ref "C21") (pin "1") (pinfunction "1_1") (pintype "passive"))
      (node (ref "C22") (pin "1") (pinfunction "1_1") (pintype "passive"))
      (node (ref "C23") (pin "1") (pinfunction "1_1") (pintype "passive"))
      (node (ref "C24") (pin "1") (pinfunction "1_1") (pintype "passive"))
      (node (ref "C25") (pin "+") (pinfunction "+_+") (pintype "passive"))
      (node (ref "C26") (pin "+") (pinfunction "+_+") (pintype "passive"))
      (node (ref "C27") (pin "+") (pinfunction "+_+") (pintype "passive"))
      (node (ref "C28") (pin "+") (pinfunction "+_+") (pintype "passive"))
      (node (ref "C3") (pin "1") (pinfunction "1_1") (pintype "passive"))
      (node (ref "C4") (pin "1") (pinfunction "1_1") (pintype "passive"))
      (node (ref "C5") (pin "1") (pinfunction "1_1") (pintype "passive"))
      (node (ref "C6") (pin "1") (pinfunction "1_1") (pintype "passive"))
      (node (ref "C7") (pin "1") (pinfunction "1_1") (pintype "passive"))
      (node (ref "C8") (pin "1") (pinfunction "1_1") (pintype "passive"))
      (node (ref "C9") (pin "1") (pinfunction "1_1") (pintype "passive"))
      (node (ref "E5") (pin "10") (pinfunction "10_10") (pintype "passive"))
      (node (ref "U$2") (pin "AA2") (pinfunction "1_AA2") (pintype "bidirectional"))
      (node (ref "U$2") (pin "BA2") (pinfunction "1_BA2") (pintype "bidirectional"))
    )
    (net (code "557") (name "VCC1") (class "Default")
      (node (ref "E24") (pin "12") (pinfunction "VCC1_12") (pintype "input"))
    )
    (net (code "558") (name "VCC2") (class "Default")
      (node (ref "E24") (pin "22") (pinfunction "VCC2_22") (pintype "input"))
    )
    (net (code "559") (name "VCC3") (class "Default")
      (node (ref "E24") (pin "23") (pinfunction "VCC3_23") (pintype "input"))
    )
    (net (code "560") (name "VDD") (class "Default")
      (node (ref "E24") (pin "24") (pinfunction "VDD_24") (pintype "input"))
      (node (ref "E5") (pin "1") (pinfunction "1_1") (pintype "passive"))
    )
    (net (code "561") (name "VGG") (class "Default")
      (node (ref "E24") (pin "16") (pinfunction "VGG_16") (pintype "input"))
      (node (ref "E25") (pin "16") (pinfunction "VGG_16") (pintype "input"))
    )
    (net (code "562") (name "~{CS}") (class "Default")
      (node (ref "E24") (pin "14") (pinfunction "~{CS}_14") (pintype "input"))
    )
  )
)
